# hackeeg-shield.net
KiCad netlist of a schematic drawn in EAGLE
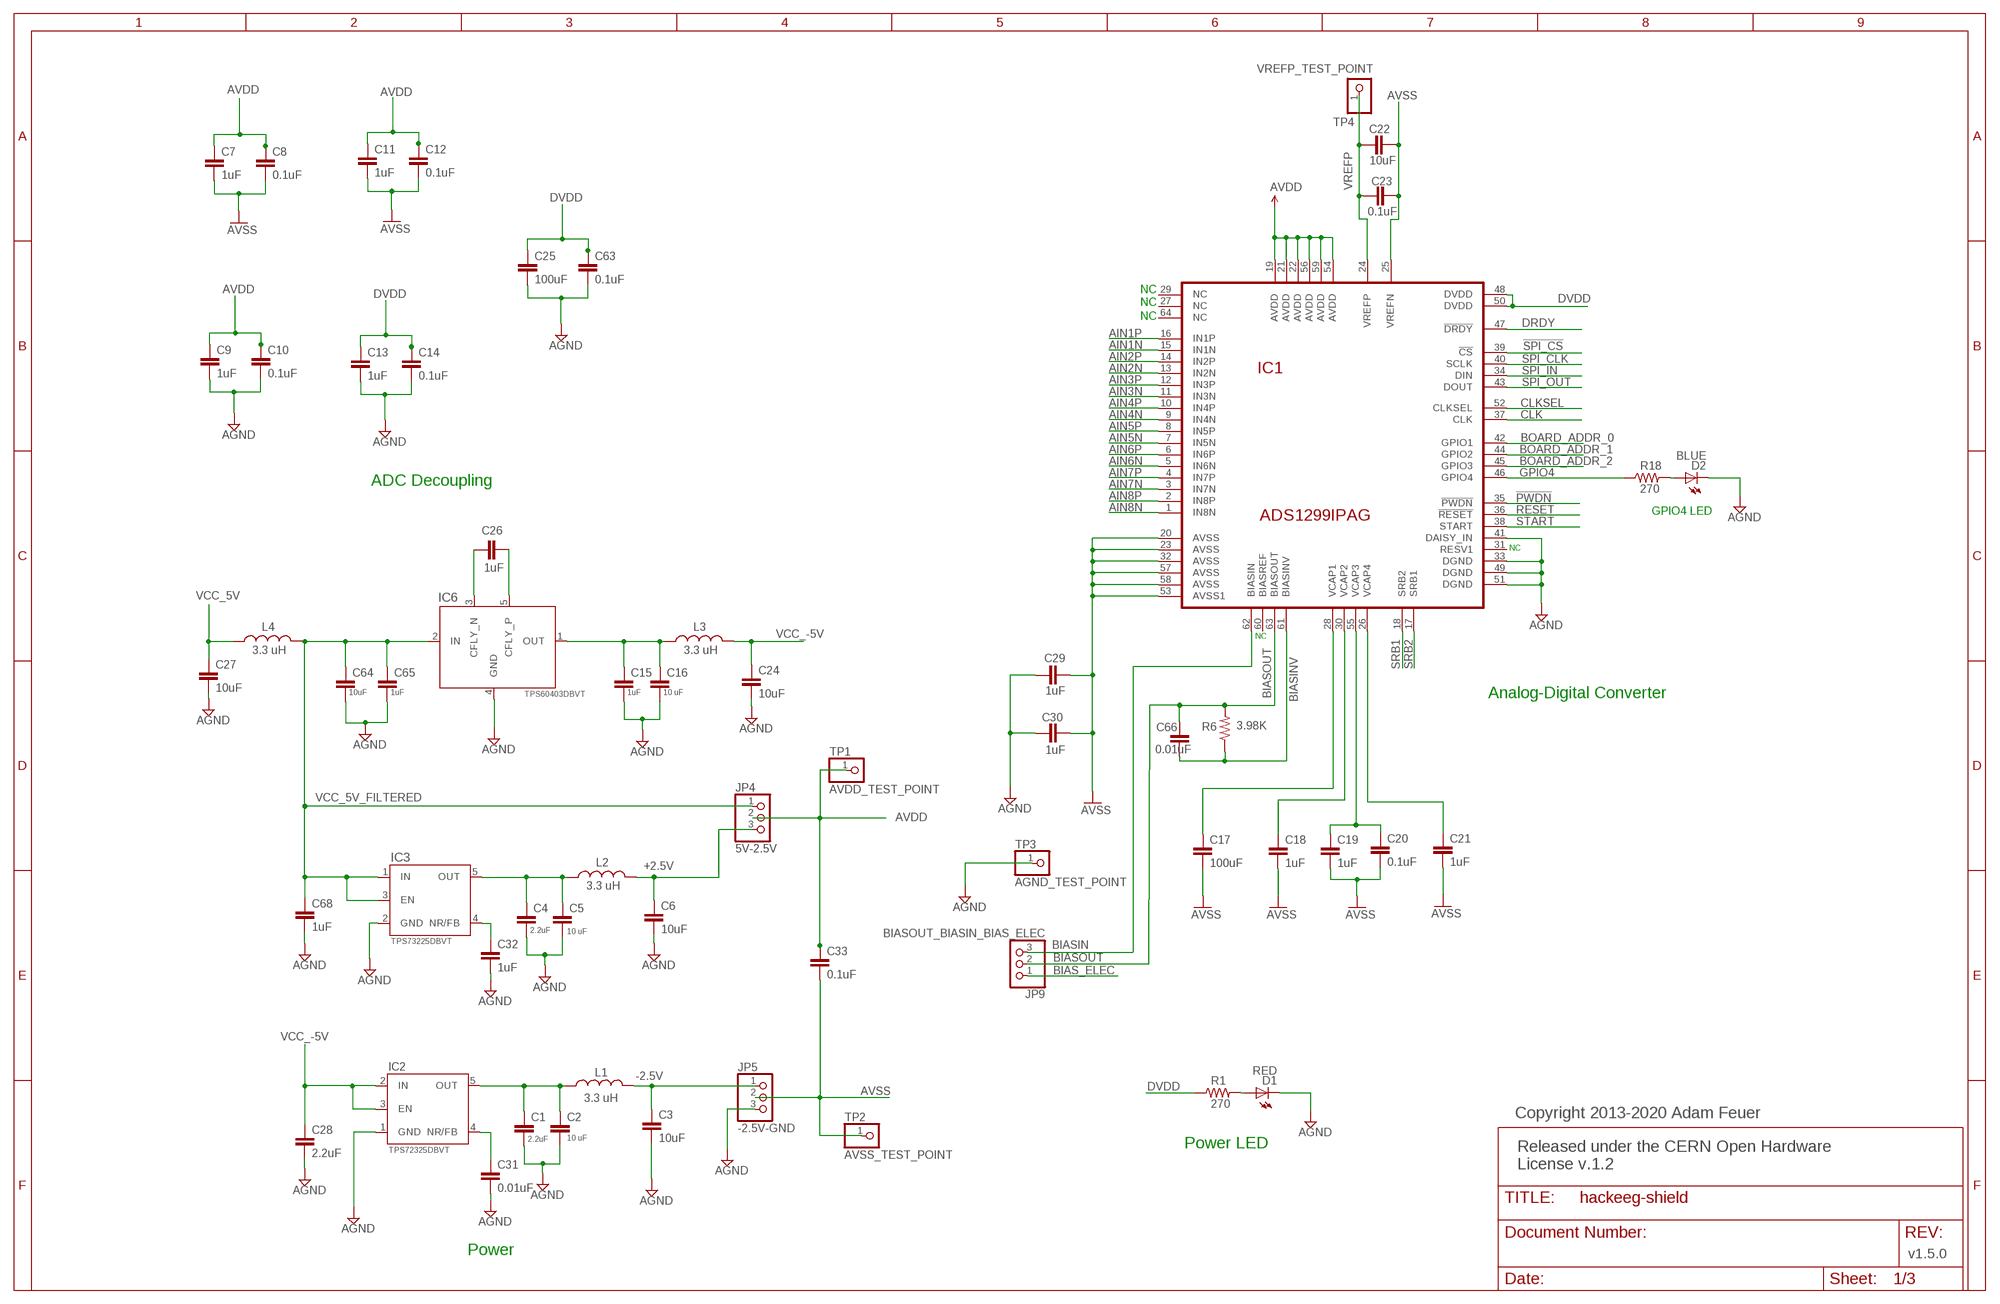
[diagram p0: schematic, sheet 1]
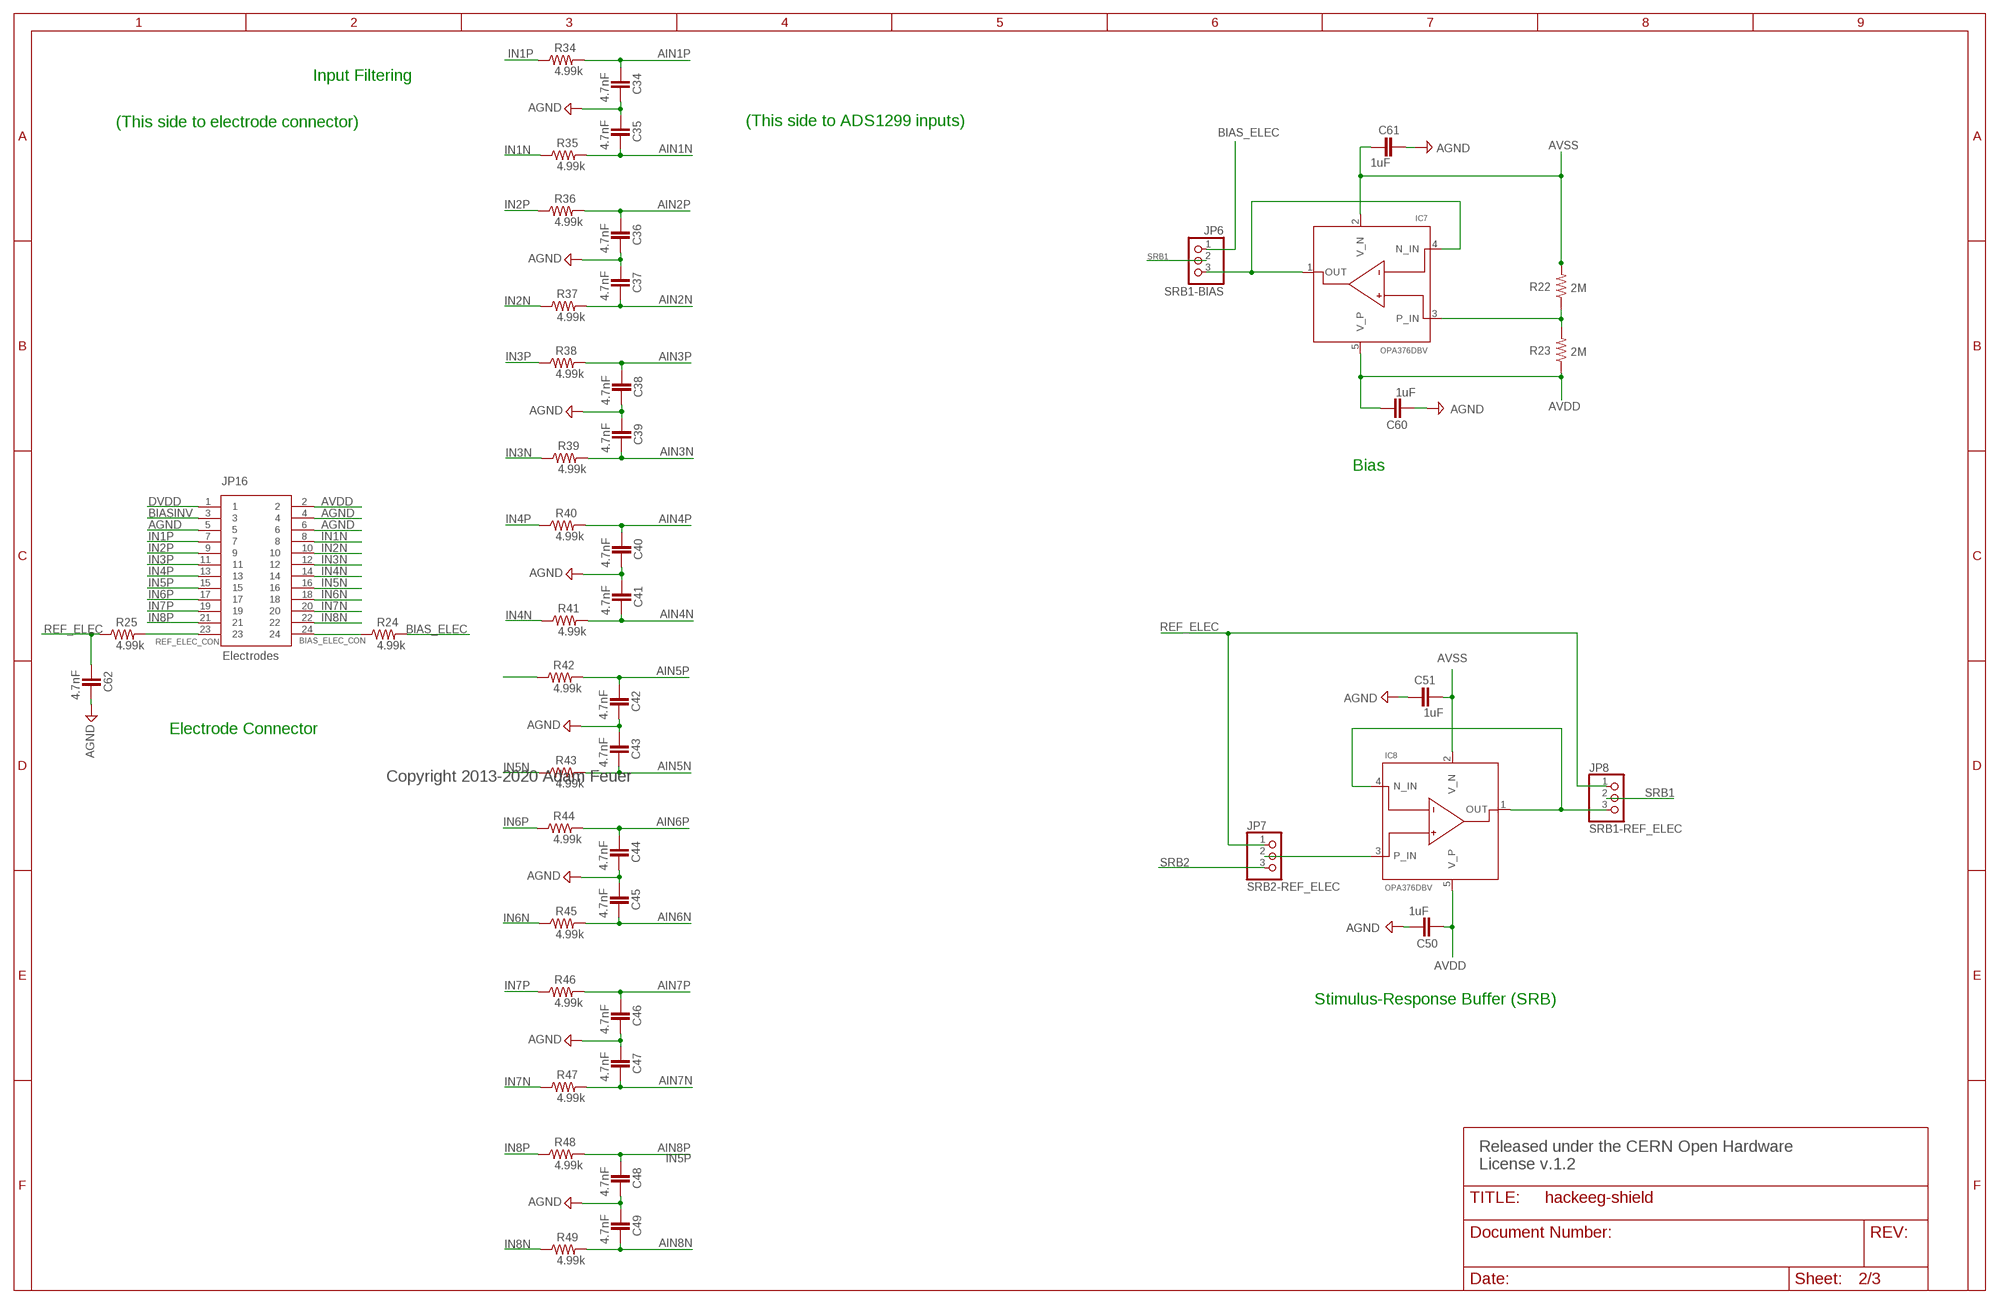
[diagram p1: schematic, sheet 2]
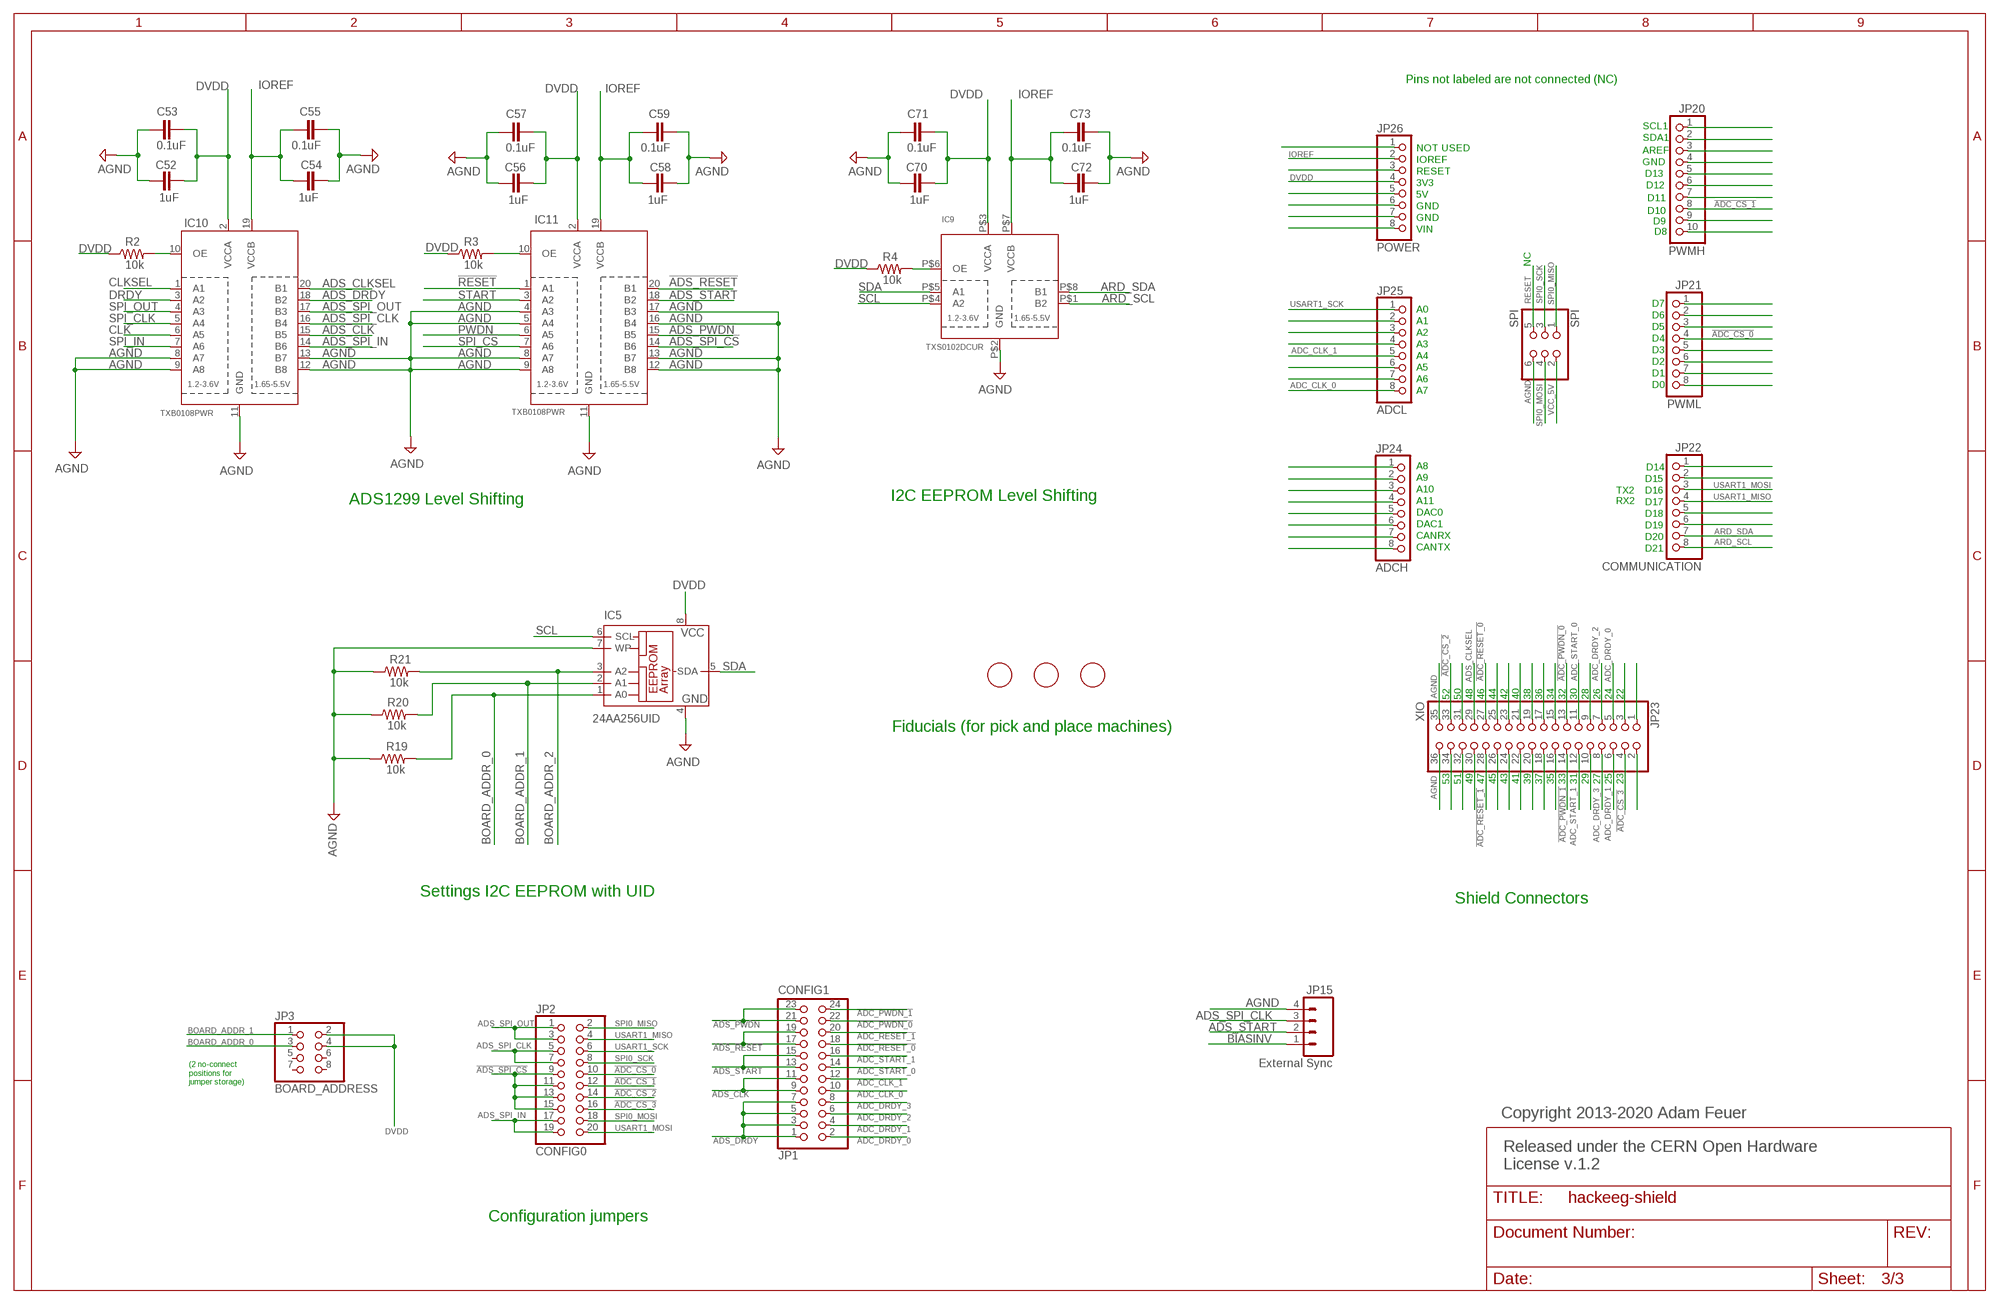
[diagram p2: schematic, sheet 3]

(export (version "E")
  (design (tool "Eeschema 10.0.6"))
  (components
    (comp (ref "C52")
      (value "1uF")
      (footprint "eagle-import:0603-CAP")
      (libsource (lib "eagle-import") (part "CAP0603-CAP"))
    )
    (comp (ref "C53")
      (value "0.1uF")
      (footprint "eagle-import:0603-CAP")
      (libsource (lib "eagle-import") (part "CAP0603-CAP"))
    )
    (comp (ref "C54")
      (value "1uF")
      (footprint "eagle-import:0603-CAP")
      (libsource (lib "eagle-import") (part "CAP0603-CAP"))
    )
    (comp (ref "C55")
      (value "0.1uF")
      (footprint "eagle-import:0603-CAP")
      (libsource (lib "eagle-import") (part "CAP0603-CAP"))
    )
    (comp (ref "C56")
      (value "1uF")
      (footprint "eagle-import:0603-CAP")
      (libsource (lib "eagle-import") (part "CAP0603-CAP"))
    )
    (comp (ref "C57")
      (value "0.1uF")
      (footprint "eagle-import:0603-CAP")
      (libsource (lib "eagle-import") (part "CAP0603-CAP"))
    )
    (comp (ref "C58")
      (value "1uF")
      (footprint "eagle-import:0603-CAP")
      (libsource (lib "eagle-import") (part "CAP0603-CAP"))
    )
    (comp (ref "C59")
      (value "0.1uF")
      (footprint "eagle-import:0603-CAP")
      (libsource (lib "eagle-import") (part "CAP0603-CAP"))
    )
    (comp (ref "C70")
      (value "1uF")
      (footprint "eagle-import:0603-CAP")
      (libsource (lib "eagle-import") (part "CAP0603-CAP"))
    )
    (comp (ref "C71")
      (value "0.1uF")
      (footprint "eagle-import:0603-CAP")
      (libsource (lib "eagle-import") (part "CAP0603-CAP"))
    )
    (comp (ref "C72")
      (value "1uF")
      (footprint "eagle-import:0603-CAP")
      (libsource (lib "eagle-import") (part "CAP0603-CAP"))
    )
    (comp (ref "C73")
      (value "0.1uF")
      (footprint "eagle-import:0603-CAP")
      (libsource (lib "eagle-import") (part "CAP0603-CAP"))
    )
    (comp (ref "IC5")
      (value "24AA256UID")
      (footprint "eagle-import:SO-08")
      (fields (field (name "MF") "MICROCHIP") (field (name "MPN") "24LC256-I/SN"))
      (libsource (lib "eagle-import") (part "24SNLC256"))
    )
    (comp (ref "IC9")
      (value "TXS0102DCUR")
      (footprint "eagle-import:VFSOP-8")
      (libsource (lib "eagle-import") (part "TXS0102"))
    )
    (comp (ref "IC10")
      (value "TXB0108PWR")
      (footprint "eagle-import:TSSOP20")
      (libsource (lib "eagle-import") (part "TXB0108PWR"))
    )
    (comp (ref "IC11")
      (value "TXB0108PWR")
      (footprint "eagle-import:TSSOP20")
      (libsource (lib "eagle-import") (part "TXB0108PWR"))
    )
    (comp (ref "JP1")
      (value "CONFIG1")
      (footprint "eagle-import:2X12")
      (libsource (lib "eagle-import") (part "PINHD-2X12"))
    )
    (comp (ref "JP2")
      (value "CONFIG0")
      (footprint "eagle-import:2X10")
      (libsource (lib "eagle-import") (part "PINHD-2X10"))
    )
    (comp (ref "JP3")
      (value "BOARD_ADDRESS")
      (footprint "eagle-import:2X04")
      (libsource (lib "eagle-import") (part "PINHD-2X4"))
    )
    (comp (ref "JP15")
      (value "External Sync")
      (footprint "eagle-import:JST-4-PTH")
      (libsource (lib "eagle-import") (part "M04JST-PTH"))
    )
    (comp (ref "JP20")
      (value "PWMH")
      (footprint "eagle-import:1X10")
      (libsource (lib "eagle-import") (part "PINHD-1X10"))
    )
    (comp (ref "JP21")
      (value "PWML")
      (footprint "eagle-import:1X08")
      (libsource (lib "eagle-import") (part "PINHD-1X8"))
    )
    (comp (ref "JP22")
      (value "COMMUNICATION")
      (footprint "eagle-import:1X08")
      (libsource (lib "eagle-import") (part "PINHD-1X8"))
    )
    (comp (ref "JP23")
      (value "XIO")
      (footprint "eagle-import:2X18")
      (libsource (lib "eagle-import") (part "PINHD-2X18"))
    )
    (comp (ref "JP24")
      (value "ADCH")
      (footprint "eagle-import:1X08")
      (libsource (lib "eagle-import") (part "PINHD-1X8"))
    )
    (comp (ref "JP25")
      (value "ADCL")
      (footprint "eagle-import:1X08")
      (libsource (lib "eagle-import") (part "PINHD-1X8"))
    )
    (comp (ref "JP26")
      (value "POWER")
      (footprint "eagle-import:1X08")
      (libsource (lib "eagle-import") (part "PINHD-1X8"))
    )
    (comp (ref "R2")
      (value "10k")
      (footprint "eagle-import:0603-RES")
      (libsource (lib "eagle-import") (part "RESISTOR0603-RES"))
    )
    (comp (ref "R3")
      (value "10k")
      (footprint "eagle-import:0603-RES")
      (libsource (lib "eagle-import") (part "RESISTOR0603-RES"))
    )
    (comp (ref "R4")
      (value "10k")
      (footprint "eagle-import:0603-RES")
      (libsource (lib "eagle-import") (part "RESISTOR0603-RES"))
    )
    (comp (ref "R19")
      (value "10k")
      (footprint "eagle-import:0603-RES")
      (libsource (lib "eagle-import") (part "RESISTOR0603-RES"))
    )
    (comp (ref "R20")
      (value "10k")
      (footprint "eagle-import:0603-RES")
      (libsource (lib "eagle-import") (part "RESISTOR0603-RES"))
    )
    (comp (ref "R21")
      (value "10k")
      (footprint "eagle-import:0603-RES")
      (libsource (lib "eagle-import") (part "RESISTOR0603-RES"))
    )
    (comp (ref "SPI")
      (value "SPI")
      (footprint "eagle-import:2X03")
      (libsource (lib "eagle-import") (part "PINHD-2X3"))
    )
    (comp (ref "U$2")
      (value "FIDUCIAL")
      (footprint "eagle-import:FIDUCIAL_1MM")
      (libsource (lib "eagle-import") (part "FIDUCIAL"))
    )
    (comp (ref "U$5")
      (value "FIDUCIAL")
      (footprint "eagle-import:FIDUCIAL_1MM")
      (libsource (lib "eagle-import") (part "FIDUCIAL"))
    )
    (comp (ref "U$6")
      (value "FIDUCIAL")
      (footprint "eagle-import:FIDUCIAL_1MM")
      (libsource (lib "eagle-import") (part "FIDUCIAL"))
    )
    (comp (ref "C1")
      (value "2.2uF")
      (footprint "eagle-import:0603-CAP")
      (libsource (lib "eagle-import") (part "CAP0603-CAP"))
    )
    (comp (ref "C2")
      (value "10 uF")
      (footprint "eagle-import:0603-CAP")
      (libsource (lib "eagle-import") (part "CAP0603-CAP"))
    )
    (comp (ref "C3")
      (value "10uF")
      (footprint "eagle-import:0603-CAP")
      (libsource (lib "eagle-import") (part "CAP0603-CAP"))
    )
    (comp (ref "C4")
      (value "2.2uF")
      (footprint "eagle-import:0603-CAP")
      (libsource (lib "eagle-import") (part "CAP0603-CAP"))
    )
    (comp (ref "C5")
      (value "10 uF")
      (footprint "eagle-import:0603-CAP")
      (libsource (lib "eagle-import") (part "CAP0603-CAP"))
    )
    (comp (ref "C6")
      (value "10uF")
      (footprint "eagle-import:0603-CAP")
      (libsource (lib "eagle-import") (part "CAP0603-CAP"))
    )
    (comp (ref "C7")
      (value "1uF")
      (footprint "eagle-import:0603-CAP")
      (libsource (lib "eagle-import") (part "CAP0603-CAP"))
    )
    (comp (ref "C8")
      (value "0.1uF")
      (footprint "eagle-import:0603-CAP")
      (libsource (lib "eagle-import") (part "CAP0603-CAP"))
    )
    (comp (ref "C9")
      (value "1uF")
      (footprint "eagle-import:0603-CAP")
      (libsource (lib "eagle-import") (part "CAP0603-CAP"))
    )
    (comp (ref "C10")
      (value "0.1uF")
      (footprint "eagle-import:0603-CAP")
      (libsource (lib "eagle-import") (part "CAP0603-CAP"))
    )
    (comp (ref "C11")
      (value "1uF")
      (footprint "eagle-import:0603-CAP")
      (libsource (lib "eagle-import") (part "CAP0603-CAP"))
    )
    (comp (ref "C12")
      (value "0.1uF")
      (footprint "eagle-import:0603-CAP")
      (libsource (lib "eagle-import") (part "CAP0603-CAP"))
    )
    (comp (ref "C13")
      (value "1uF")
      (footprint "eagle-import:0603-CAP")
      (libsource (lib "eagle-import") (part "CAP0603-CAP"))
    )
    (comp (ref "C14")
      (value "0.1uF")
      (footprint "eagle-import:0603-CAP")
      (libsource (lib "eagle-import") (part "CAP0603-CAP"))
    )
    (comp (ref "C15")
      (value "1uF")
      (footprint "eagle-import:0603-CAP")
      (libsource (lib "eagle-import") (part "CAP0603-CAP"))
    )
    (comp (ref "C16")
      (value "10 uF")
      (footprint "eagle-import:0603-CAP")
      (libsource (lib "eagle-import") (part "CAP0603-CAP"))
    )
    (comp (ref "C17")
      (value "100uF")
      (footprint "eagle-import:1210")
      (libsource (lib "eagle-import") (part "CAP1210"))
    )
    (comp (ref "C18")
      (value "1uF")
      (footprint "eagle-import:0603-CAP")
      (libsource (lib "eagle-import") (part "CAP0603-CAP"))
    )
    (comp (ref "C19")
      (value "1uF")
      (footprint "eagle-import:0603-CAP")
      (libsource (lib "eagle-import") (part "CAP0603-CAP"))
    )
    (comp (ref "C20")
      (value "0.1uF")
      (footprint "eagle-import:0603-CAP")
      (libsource (lib "eagle-import") (part "CAP0603-CAP"))
    )
    (comp (ref "C21")
      (value "1uF")
      (footprint "eagle-import:0603-CAP")
      (libsource (lib "eagle-import") (part "CAP0603-CAP"))
    )
    (comp (ref "C22")
      (value "10uF")
      (footprint "eagle-import:0603-CAP")
      (libsource (lib "eagle-import") (part "CAP0603-CAP"))
    )
    (comp (ref "C23")
      (value "0.1uF")
      (footprint "eagle-import:0603-CAP")
      (libsource (lib "eagle-import") (part "CAP0603-CAP"))
    )
    (comp (ref "C24")
      (value "10uF")
      (footprint "eagle-import:0603-CAP")
      (libsource (lib "eagle-import") (part "CAP0603-CAP"))
    )
    (comp (ref "C25")
      (value "100uF")
      (footprint "eagle-import:1210")
      (libsource (lib "eagle-import") (part "CAP1210"))
    )
    (comp (ref "C26")
      (value "1uF")
      (footprint "eagle-import:0603-CAP")
      (libsource (lib "eagle-import") (part "CAP0603-CAP"))
    )
    (comp (ref "C27")
      (value "10uF")
      (footprint "eagle-import:0603-CAP")
      (libsource (lib "eagle-import") (part "CAP0603-CAP"))
    )
    (comp (ref "C28")
      (value "2.2uF")
      (footprint "eagle-import:0603-CAP")
      (libsource (lib "eagle-import") (part "CAP0603-CAP"))
    )
    (comp (ref "C29")
      (value "1uF")
      (footprint "eagle-import:0603-CAP")
      (libsource (lib "eagle-import") (part "CAP0603-CAP"))
    )
    (comp (ref "C30")
      (value "1uF")
      (footprint "eagle-import:0603-CAP")
      (libsource (lib "eagle-import") (part "CAP0603-CAP"))
    )
    (comp (ref "C31")
      (value "0.01uF")
      (footprint "eagle-import:0603-CAP")
      (libsource (lib "eagle-import") (part "CAP0603-CAP"))
    )
    (comp (ref "C32")
      (value "1uF")
      (footprint "eagle-import:0603-CAP")
      (libsource (lib "eagle-import") (part "CAP0603-CAP"))
    )
    (comp (ref "C33")
      (value "0.1uF")
      (footprint "eagle-import:0603-CAP")
      (libsource (lib "eagle-import") (part "CAP0603-CAP"))
    )
    (comp (ref "C63")
      (value "0.1uF")
      (footprint "eagle-import:0603-CAP")
      (libsource (lib "eagle-import") (part "CAP0603-CAP"))
    )
    (comp (ref "C64")
      (value "10uF")
      (footprint "eagle-import:0603-CAP")
      (libsource (lib "eagle-import") (part "CAP0603-CAP"))
    )
    (comp (ref "C65")
      (value "1uF")
      (footprint "eagle-import:0603-CAP")
      (libsource (lib "eagle-import") (part "CAP0603-CAP"))
    )
    (comp (ref "C66")
      (value "0.01uF")
      (footprint "eagle-import:0603-CAP")
      (libsource (lib "eagle-import") (part "CAP0603-CAP"))
    )
    (comp (ref "C68")
      (value "1uF")
      (footprint "eagle-import:0603-CAP")
      (libsource (lib "eagle-import") (part "CAP0603-CAP"))
    )
    (comp (ref "D1")
      (value "RED")
      (footprint "eagle-import:LED-1206")
      (libsource (lib "eagle-import") (part "LED-RED1206"))
    )
    (comp (ref "D2")
      (value "BLUE")
      (footprint "eagle-import:LED-1206")
      (libsource (lib "eagle-import") (part "LED-WHITE"))
    )
    (comp (ref "IC1")
      (value "ADS1299IPAG")
      (footprint "eagle-import:TQFP64")
      (libsource (lib "eagle-import") (part "ADS1299PAG"))
    )
    (comp (ref "IC2")
      (value "TPS72325DBVT")
      (footprint "eagle-import:SOT23-5")
      (libsource (lib "eagle-import") (part "TPS723xx_TPS732XXDBV"))
    )
    (comp (ref "IC3")
      (value "TPS73225DBVT")
      (footprint "eagle-import:SOT23-5")
      (libsource (lib "eagle-import") (part "TPS732XXDBV"))
    )
    (comp (ref "IC6")
      (value "TPS60403DBVT")
      (footprint "eagle-import:SOT23-5")
      (libsource (lib "eagle-import") (part "TPS604XXDBV"))
    )
    (comp (ref "JP4")
      (value "5V-2.5V")
      (footprint "eagle-import:1X03")
      (libsource (lib "eagle-import") (part "headers_PINHD-1X3"))
    )
    (comp (ref "JP5")
      (value "-2.5V-GND")
      (footprint "eagle-import:1X03")
      (libsource (lib "eagle-import") (part "headers_PINHD-1X3"))
    )
    (comp (ref "JP9")
      (value "BIASOUT_BIASIN_BIAS_ELEC")
      (footprint "eagle-import:1X03")
      (libsource (lib "eagle-import") (part "headers_PINHD-1X3"))
    )
    (comp (ref "L1")
      (value "3.3 uH")
      (footprint "eagle-import:0805")
      (libsource (lib "eagle-import") (part "INDUCTOR0805"))
    )
    (comp (ref "L2")
      (value "3.3 uH")
      (footprint "eagle-import:0805")
      (libsource (lib "eagle-import") (part "INDUCTOR0805"))
    )
    (comp (ref "L3")
      (value "3.3 uH")
      (footprint "eagle-import:0805")
      (libsource (lib "eagle-import") (part "INDUCTOR0805"))
    )
    (comp (ref "L4")
      (value "3.3 uH")
      (footprint "eagle-import:0805")
      (libsource (lib "eagle-import") (part "INDUCTOR0805"))
    )
    (comp (ref "R1")
      (value "270")
      (footprint "eagle-import:0603-RES")
      (libsource (lib "eagle-import") (part "RESISTOR0603-RES"))
    )
    (comp (ref "R6")
      (value "3.98K")
      (footprint "eagle-import:0603-RES")
      (libsource (lib "eagle-import") (part "RESISTOR0603-RES"))
    )
    (comp (ref "R18")
      (value "270")
      (footprint "eagle-import:0603-RES")
      (libsource (lib "eagle-import") (part "RESISTOR0603-RES"))
    )
    (comp (ref "TP1")
      (value "AVDD_TEST_POINT")
      (footprint "eagle-import:1X01")
      (libsource (lib "eagle-import") (part "PINHD-1X1"))
    )
    (comp (ref "TP2")
      (value "AVSS_TEST_POINT")
      (footprint "eagle-import:1X01")
      (libsource (lib "eagle-import") (part "PINHD-1X1"))
    )
    (comp (ref "TP3")
      (value "AGND_TEST_POINT")
      (footprint "eagle-import:1X01")
      (libsource (lib "eagle-import") (part "PINHD-1X1"))
    )
    (comp (ref "TP4")
      (value "VREFP_TEST_POINT")
      (footprint "eagle-import:1X01")
      (libsource (lib "eagle-import") (part "PINHD-1X1"))
    )
    (comp (ref "C34")
      (value "4.7nF")
      (footprint "eagle-import:0603-CAP")
      (libsource (lib "eagle-import") (part "CAP0603-CAP"))
    )
    (comp (ref "C35")
      (value "4.7nF")
      (footprint "eagle-import:0603-CAP")
      (libsource (lib "eagle-import") (part "CAP0603-CAP"))
    )
    (comp (ref "C36")
      (value "4.7nF")
      (footprint "eagle-import:0603-CAP")
      (libsource (lib "eagle-import") (part "CAP0603-CAP"))
    )
    (comp (ref "C37")
      (value "4.7nF")
      (footprint "eagle-import:0603-CAP")
      (libsource (lib "eagle-import") (part "CAP0603-CAP"))
    )
    (comp (ref "C38")
      (value "4.7nF")
      (footprint "eagle-import:0603-CAP")
      (libsource (lib "eagle-import") (part "CAP0603-CAP"))
    )
    (comp (ref "C39")
      (value "4.7nF")
      (footprint "eagle-import:0603-CAP")
      (libsource (lib "eagle-import") (part "CAP0603-CAP"))
    )
    (comp (ref "C40")
      (value "4.7nF")
      (footprint "eagle-import:0603-CAP")
      (libsource (lib "eagle-import") (part "CAP0603-CAP"))
    )
    (comp (ref "C41")
      (value "4.7nF")
      (footprint "eagle-import:0603-CAP")
      (libsource (lib "eagle-import") (part "CAP0603-CAP"))
    )
    (comp (ref "C42")
      (value "4.7nF")
      (footprint "eagle-import:0603-CAP")
      (libsource (lib "eagle-import") (part "CAP0603-CAP"))
    )
    (comp (ref "C43")
      (value "4.7nF")
      (footprint "eagle-import:0603-CAP")
      (libsource (lib "eagle-import") (part "CAP0603-CAP"))
    )
    (comp (ref "C44")
      (value "4.7nF")
      (footprint "eagle-import:0603-CAP")
      (libsource (lib "eagle-import") (part "CAP0603-CAP"))
    )
    (comp (ref "C45")
      (value "4.7nF")
      (footprint "eagle-import:0603-CAP")
      (libsource (lib "eagle-import") (part "CAP0603-CAP"))
    )
    (comp (ref "C46")
      (value "4.7nF")
      (footprint "eagle-import:0603-CAP")
      (libsource (lib "eagle-import") (part "CAP0603-CAP"))
    )
    (comp (ref "C47")
      (value "4.7nF")
      (footprint "eagle-import:0603-CAP")
      (libsource (lib "eagle-import") (part "CAP0603-CAP"))
    )
    (comp (ref "C48")
      (value "4.7nF")
      (footprint "eagle-import:0603-CAP")
      (libsource (lib "eagle-import") (part "CAP0603-CAP"))
    )
    (comp (ref "C49")
      (value "4.7nF")
      (footprint "eagle-import:0603-CAP")
      (libsource (lib "eagle-import") (part "CAP0603-CAP"))
    )
    (comp (ref "C50")
      (value "1uF")
      (footprint "eagle-import:0603-CAP")
      (libsource (lib "eagle-import") (part "CAP0603-CAP"))
    )
    (comp (ref "C51")
      (value "1uF")
      (footprint "eagle-import:0603-CAP")
      (libsource (lib "eagle-import") (part "CAP0603-CAP"))
    )
    (comp (ref "C60")
      (value "1uF")
      (footprint "eagle-import:0603-CAP")
      (libsource (lib "eagle-import") (part "CAP0603-CAP"))
    )
    (comp (ref "C61")
      (value "1uF")
      (footprint "eagle-import:0603-CAP")
      (libsource (lib "eagle-import") (part "CAP0603-CAP"))
    )
    (comp (ref "C62")
      (value "4.7nF")
      (footprint "eagle-import:0603-CAP")
      (libsource (lib "eagle-import") (part "CAP0603-CAP"))
    )
    (comp (ref "IC7")
      (value "OPA376DBV")
      (footprint "eagle-import:SOT23-5")
      (libsource (lib "eagle-import") (part "OPA376DBV"))
    )
    (comp (ref "IC8")
      (value "OPA376DBV")
      (footprint "eagle-import:SOT23-5")
      (libsource (lib "eagle-import") (part "OPA376DBV"))
    )
    (comp (ref "JP6")
      (value "SRB1-BIAS")
      (footprint "eagle-import:1X03")
      (libsource (lib "eagle-import") (part "PINHD-1X3"))
    )
    (comp (ref "JP7")
      (value "SRB2-REF_ELEC")
      (footprint "eagle-import:1X03")
      (libsource (lib "eagle-import") (part "PINHD-1X3"))
    )
    (comp (ref "JP8")
      (value "SRB1-REF_ELEC")
      (footprint "eagle-import:1X03")
      (libsource (lib "eagle-import") (part "PINHD-1X3"))
    )
    (comp (ref "JP16")
      (value "Electrodes")
      (footprint "eagle-import:OST_302-R241")
      (fields (field (name "MF") "On Shore") (field (name "MP") "302-R241"))
      (libsource (lib "eagle-import") (part "302-R241"))
    )
    (comp (ref "R22")
      (value "2M")
      (footprint "eagle-import:0603-RES")
      (libsource (lib "eagle-import") (part "RESISTOR0603-RES"))
    )
    (comp (ref "R23")
      (value "2M")
      (footprint "eagle-import:0603-RES")
      (libsource (lib "eagle-import") (part "RESISTOR0603-RES"))
    )
    (comp (ref "R24")
      (value "4.99k")
      (footprint "eagle-import:0603-RES")
      (libsource (lib "eagle-import") (part "RESISTOR0603-RES"))
    )
    (comp (ref "R25")
      (value "4.99k")
      (footprint "eagle-import:0603-RES")
      (libsource (lib "eagle-import") (part "RESISTOR0603-RES"))
    )
    (comp (ref "R34")
      (value "4.99k")
      (footprint "eagle-import:0603-RES")
      (libsource (lib "eagle-import") (part "RESISTOR0603-RES"))
    )
    (comp (ref "R35")
      (value "4.99k")
      (footprint "eagle-import:0603-RES")
      (libsource (lib "eagle-import") (part "RESISTOR0603-RES"))
    )
    (comp (ref "R36")
      (value "4.99k")
      (footprint "eagle-import:0603-RES")
      (libsource (lib "eagle-import") (part "RESISTOR0603-RES"))
    )
    (comp (ref "R37")
      (value "4.99k")
      (footprint "eagle-import:0603-RES")
      (libsource (lib "eagle-import") (part "RESISTOR0603-RES"))
    )
    (comp (ref "R38")
      (value "4.99k")
      (footprint "eagle-import:0603-RES")
      (libsource (lib "eagle-import") (part "RESISTOR0603-RES"))
    )
    (comp (ref "R39")
      (value "4.99k")
      (footprint "eagle-import:0603-RES")
      (libsource (lib "eagle-import") (part "RESISTOR0603-RES"))
    )
    (comp (ref "R40")
      (value "4.99k")
      (footprint "eagle-import:0603-RES")
      (libsource (lib "eagle-import") (part "RESISTOR0603-RES"))
    )
    (comp (ref "R41")
      (value "4.99k")
      (footprint "eagle-import:0603-RES")
      (libsource (lib "eagle-import") (part "RESISTOR0603-RES"))
    )
    (comp (ref "R42")
      (value "4.99k")
      (footprint "eagle-import:0603-RES")
      (libsource (lib "eagle-import") (part "RESISTOR0603-RES"))
    )
    (comp (ref "R43")
      (value "4.99k")
      (footprint "eagle-import:0603-RES")
      (libsource (lib "eagle-import") (part "RESISTOR0603-RES"))
    )
    (comp (ref "R44")
      (value "4.99k")
      (footprint "eagle-import:0603-RES")
      (libsource (lib "eagle-import") (part "RESISTOR0603-RES"))
    )
    (comp (ref "R45")
      (value "4.99k")
      (footprint "eagle-import:0603-RES")
      (libsource (lib "eagle-import") (part "RESISTOR0603-RES"))
    )
    (comp (ref "R46")
      (value "4.99k")
      (footprint "eagle-import:0603-RES")
      (libsource (lib "eagle-import") (part "RESISTOR0603-RES"))
    )
    (comp (ref "R47")
      (value "4.99k")
      (footprint "eagle-import:0603-RES")
      (libsource (lib "eagle-import") (part "RESISTOR0603-RES"))
    )
    (comp (ref "R48")
      (value "4.99k")
      (footprint "eagle-import:0603-RES")
      (libsource (lib "eagle-import") (part "RESISTOR0603-RES"))
    )
    (comp (ref "R49")
      (value "4.99k")
      (footprint "eagle-import:0603-RES")
      (libsource (lib "eagle-import") (part "RESISTOR0603-RES"))
    )
  )
  (nets
    (net (code "1") (name "+2.5V") (class "Default")
      (node (ref "C6") (pin "1") (pinfunction "1_1") (pintype "passive"))
      (node (ref "JP4") (pin "3") (pinfunction "3_3") (pintype "passive"))
      (node (ref "L2") (pin "2") (pinfunction "2_2") (pintype "passive"))
    )
    (net (code "2") (name "-2.5V") (class "Default")
      (node (ref "C3") (pin "1") (pinfunction "1_1") (pintype "passive"))
      (node (ref "JP5") (pin "1") (pinfunction "1_1") (pintype "passive"))
      (node (ref "L1") (pin "2") (pinfunction "2_2") (pintype "passive"))
    )
    (net (code "3") (name "ADC_CLK_0") (class "Default")
      (node (ref "JP1") (pin "10") (pinfunction "10_10") (pintype "passive"))
      (node (ref "JP25") (pin "8") (pinfunction "8_8") (pintype "passive"))
    )
    (net (code "4") (name "ADC_CLK_1") (class "Default")
      (node (ref "JP1") (pin "12") (pinfunction "12_12") (pintype "passive"))
      (node (ref "JP25") (pin "5") (pinfunction "5_5") (pintype "passive"))
    )
    (net (code "5") (name "ADC_DRDY_0") (class "Default")
      (node (ref "JP1") (pin "2") (pinfunction "2_2") (pintype "passive"))
      (node (ref "JP23") (pin "5") (pinfunction "5_5") (pintype "passive"))
    )
    (net (code "6") (name "ADC_DRDY_1") (class "Default")
      (node (ref "JP1") (pin "4") (pinfunction "4_4") (pintype "passive"))
      (node (ref "JP23") (pin "6") (pinfunction "6_6") (pintype "passive"))
    )
    (net (code "7") (name "ADC_DRDY_2") (class "Default")
      (node (ref "JP1") (pin "6") (pinfunction "6_6") (pintype "passive"))
      (node (ref "JP23") (pin "7") (pinfunction "7_7") (pintype "passive"))
    )
    (net (code "8") (name "ADC_DRDY_3") (class "Default")
      (node (ref "JP1") (pin "8") (pinfunction "8_8") (pintype "passive"))
      (node (ref "JP23") (pin "8") (pinfunction "8_8") (pintype "passive"))
    )
    (net (code "9") (name "ADC_START_0") (class "Default")
      (node (ref "JP1") (pin "14") (pinfunction "14_14") (pintype "passive"))
      (node (ref "JP23") (pin "11") (pinfunction "11_11") (pintype "passive"))
    )
    (net (code "10") (name "ADC_START_1") (class "Default")
      (node (ref "JP1") (pin "16") (pinfunction "16_16") (pintype "passive"))
      (node (ref "JP23") (pin "12") (pinfunction "12_12") (pintype "passive"))
    )
    (net (code "11") (name "ADS_CLK") (class "Default")
      (node (ref "IC10") (pin "15") (pinfunction "B5_15") (pintype "bidirectional"))
      (node (ref "JP1") (pin "11") (pinfunction "11_11") (pintype "passive"))
      (node (ref "JP1") (pin "9") (pinfunction "9_9") (pintype "passive"))
    )
    (net (code "12") (name "ADS_CLKSEL") (class "Default")
      (node (ref "IC10") (pin "20") (pinfunction "B1_20") (pintype "bidirectional"))
      (node (ref "JP23") (pin "29") (pinfunction "29_29") (pintype "passive"))
    )
    (net (code "13") (name "ADS_DRDY") (class "Default")
      (node (ref "IC10") (pin "18") (pinfunction "B2_18") (pintype "bidirectional"))
      (node (ref "JP1") (pin "1") (pinfunction "1_1") (pintype "passive"))
      (node (ref "JP1") (pin "3") (pinfunction "3_3") (pintype "passive"))
      (node (ref "JP1") (pin "5") (pinfunction "5_5") (pintype "passive"))
      (node (ref "JP1") (pin "7") (pinfunction "7_7") (pintype "passive"))
    )
    (net (code "14") (name "ADS_SPI_CLK") (class "Default")
      (node (ref "IC10") (pin "16") (pinfunction "B4_16") (pintype "bidirectional"))
      (node (ref "JP15") (pin "3") (pinfunction "3_3") (pintype "passive"))
      (node (ref "JP2") (pin "5") (pinfunction "5_5") (pintype "passive"))
      (node (ref "JP2") (pin "7") (pinfunction "7_7") (pintype "passive"))
    )
    (net (code "15") (name "ADS_SPI_IN") (class "Default")
      (node (ref "IC10") (pin "14") (pinfunction "B6_14") (pintype "bidirectional"))
      (node (ref "JP2") (pin "17") (pinfunction "17_17") (pintype "passive"))
      (node (ref "JP2") (pin "19") (pinfunction "19_19") (pintype "passive"))
    )
    (net (code "16") (name "ADS_SPI_OUT") (class "Default")
      (node (ref "IC10") (pin "17") (pinfunction "B3_17") (pintype "bidirectional"))
      (node (ref "JP2") (pin "1") (pinfunction "1_1") (pintype "passive"))
      (node (ref "JP2") (pin "3") (pinfunction "3_3") (pintype "passive"))
    )
    (net (code "17") (name "ADS_START") (class "Default")
      (node (ref "IC11") (pin "18") (pinfunction "B2_18") (pintype "bidirectional"))
      (node (ref "JP1") (pin "13") (pinfunction "13_13") (pintype "passive"))
      (node (ref "JP1") (pin "15") (pinfunction "15_15") (pintype "passive"))
      (node (ref "JP15") (pin "2") (pinfunction "2_2") (pintype "passive"))
    )
    (net (code "18") (name "AGND") (class "Default")
      (node (ref "C1") (pin "2") (pinfunction "2_2") (pintype "passive"))
      (node (ref "C10") (pin "2") (pinfunction "2_2") (pintype "passive"))
      (node (ref "C13") (pin "2") (pinfunction "2_2") (pintype "passive"))
      (node (ref "C14") (pin "2") (pinfunction "2_2") (pintype "passive"))
      (node (ref "C15") (pin "2") (pinfunction "2_2") (pintype "passive"))
      (node (ref "C16") (pin "2") (pinfunction "2_2") (pintype "passive"))
      (node (ref "C2") (pin "2") (pinfunction "2_2") (pintype "passive"))
      (node (ref "C24") (pin "2") (pinfunction "2_2") (pintype "passive"))
      (node (ref "C25") (pin "2") (pinfunction "2_2") (pintype "passive"))
      (node (ref "C27") (pin "2") (pinfunction "2_2") (pintype "passive"))
      (node (ref "C28") (pin "2") (pinfunction "2_2") (pintype "passive"))
      (node (ref "C29") (pin "1") (pinfunction "1_1") (pintype "passive"))
      (node (ref "C3") (pin "2") (pinfunction "2_2") (pintype "passive"))
      (node (ref "C30") (pin "1") (pinfunction "1_1") (pintype "passive"))
      (node (ref "C31") (pin "2") (pinfunction "2_2") (pintype "passive"))
      (node (ref "C32") (pin "2") (pinfunction "2_2") (pintype "passive"))
      (node (ref "C34") (pin "2") (pinfunction "2_2") (pintype "passive"))
      (node (ref "C35") (pin "1") (pinfunction "1_1") (pintype "passive"))
      (node (ref "C36") (pin "2") (pinfunction "2_2") (pintype "passive"))
      (node (ref "C37") (pin "1") (pinfunction "1_1") (pintype "passive"))
      (node (ref "C38") (pin "2") (pinfunction "2_2") (pintype "passive"))
      (node (ref "C39") (pin "1") (pinfunction "1_1") (pintype "passive"))
      (node (ref "C4") (pin "2") (pinfunction "2_2") (pintype "passive"))
      (node (ref "C40") (pin "2") (pinfunction "2_2") (pintype "passive"))
      (node (ref "C41") (pin "1") (pinfunction "1_1") (pintype "passive"))
      (node (ref "C42") (pin "2") (pinfunction "2_2") (pintype "passive"))
      (node (ref "C43") (pin "1") (pinfunction "1_1") (pintype "passive"))
      (node (ref "C44") (pin "2") (pinfunction "2_2") (pintype "passive"))
      (node (ref "C45") (pin "1") (pinfunction "1_1") (pintype "passive"))
      (node (ref "C46") (pin "2") (pinfunction "2_2") (pintype "passive"))
      (node (ref "C47") (pin "1") (pinfunction "1_1") (pintype "passive"))
      (node (ref "C48") (pin "2") (pinfunction "2_2") (pintype "passive"))
      (node (ref "C49") (pin "1") (pinfunction "1_1") (pintype "passive"))
      (node (ref "C5") (pin "2") (pinfunction "2_2") (pintype "passive"))
      (node (ref "C50") (pin "2") (pinfunction "2_2") (pintype "passive"))
      (node (ref "C51") (pin "1") (pinfunction "1_1") (pintype "passive"))
      (node (ref "C52") (pin "1") (pinfunction "1_1") (pintype "passive"))
      (node (ref "C53") (pin "1") (pinfunction "1_1") (pintype "passive"))
      (node (ref "C54") (pin "1") (pinfunction "1_1") (pintype "passive"))
      (node (ref "C55") (pin "1") (pinfunction "1_1") (pintype "passive"))
      (node (ref "C56") (pin "1") (pinfunction "1_1") (pintype "passive"))
      (node (ref "C57") (pin "1") (pinfunction "1_1") (pintype "passive"))
      (node (ref "C58") (pin "1") (pinfunction "1_1") (pintype "passive"))
      (node (ref "C59") (pin "1") (pinfunction "1_1") (pintype "passive"))
      (node (ref "C6") (pin "2") (pinfunction "2_2") (pintype "passive"))
      (node (ref "C60") (pin "2") (pinfunction "2_2") (pintype "passive"))
      (node (ref "C61") (pin "1") (pinfunction "1_1") (pintype "passive"))
      (node (ref "C62") (pin "2") (pinfunction "2_2") (pintype "passive"))
      (node (ref "C63") (pin "2") (pinfunction "2_2") (pintype "passive"))
      (node (ref "C64") (pin "2") (pinfunction "2_2") (pintype "passive"))
      (node (ref "C65") (pin "2") (pinfunction "2_2") (pintype "passive"))
      (node (ref "C68") (pin "2") (pinfunction "2_2") (pintype "passive"))
      (node (ref "C70") (pin "1") (pinfunction "1_1") (pintype "passive"))
      (node (ref "C71") (pin "1") (pinfunction "1_1") (pintype "passive"))
      (node (ref "C72") (pin "1") (pinfunction "1_1") (pintype "passive"))
      (node (ref "C73") (pin "1") (pinfunction "1_1") (pintype "passive"))
      (node (ref "C9") (pin "2") (pinfunction "2_2") (pintype "passive"))
      (node (ref "D1") (pin "C") (pinfunction "C_C") (pintype "passive"))
      (node (ref "D2") (pin "C") (pinfunction "C_C") (pintype "passive"))
      (node (ref "IC1") (pin "33") (pinfunction "DGND_33") (pintype "power_in"))
      (node (ref "IC1") (pin "41") (pinfunction "DAISY_IN_41") (pintype "input"))
      (node (ref "IC1") (pin "49") (pinfunction "DGND_49") (pintype "power_in"))
      (node (ref "IC1") (pin "51") (pinfunction "DGND_51") (pintype "power_in"))
      (node (ref "IC10") (pin "11") (pinfunction "GND_11") (pintype "bidirectional"))
      (node (ref "IC10") (pin "12") (pinfunction "B8_12") (pintype "bidirectional"))
      (node (ref "IC10") (pin "13") (pinfunction "B7_13") (pintype "bidirectional"))
      (node (ref "IC10") (pin "8") (pinfunction "A7_8") (pintype "bidirectional"))
      (node (ref "IC10") (pin "9") (pinfunction "A8_9") (pintype "bidirectional"))
      (node (ref "IC11") (pin "11") (pinfunction "GND_11") (pintype "bidirectional"))
      (node (ref "IC11") (pin "12") (pinfunction "B8_12") (pintype "bidirectional"))
      (node (ref "IC11") (pin "13") (pinfunction "B7_13") (pintype "bidirectional"))
      (node (ref "IC11") (pin "16") (pinfunction "B4_16") (pintype "bidirectional"))
      (node (ref "IC11") (pin "17") (pinfunction "B3_17") (pintype "bidirectional"))
      (node (ref "IC11") (pin "4") (pinfunction "A3_4") (pintype "bidirectional"))
      (node (ref "IC11") (pin "5") (pinfunction "A4_5") (pintype "bidirectional"))
      (node (ref "IC11") (pin "8") (pinfunction "A7_8") (pintype "bidirectional"))
      (node (ref "IC11") (pin "9") (pinfunction "A8_9") (pintype "bidirectional"))
      (node (ref "IC2") (pin "1") (pinfunction "GND_1") (pintype "bidirectional"))
      (node (ref "IC3") (pin "2") (pinfunction "GND_2") (pintype "bidirectional"))
      (node (ref "IC5") (pin "4") (pinfunction "GND_4") (pintype "power_in"))
      (node (ref "IC5") (pin "7") (pinfunction "WP_7") (pintype "input"))
      (node (ref "IC6") (pin "4") (pinfunction "GND_4") (pintype "bidirectional"))
      (node (ref "IC9") (pin "P$2") (pinfunction "GND_P$2") (pintype "bidirectional"))
      (node (ref "JP15") (pin "4") (pinfunction "4_4") (pintype "passive"))
      (node (ref "JP16") (pin "4") (pinfunction "4_4") (pintype "passive"))
      (node (ref "JP16") (pin "5") (pinfunction "5_5") (pintype "passive"))
      (node (ref "JP16") (pin "6") (pinfunction "6_6") (pintype "passive"))
      (node (ref "JP23") (pin "35") (pinfunction "35_35") (pintype "passive"))
      (node (ref "JP23") (pin "36") (pinfunction "36_36") (pintype "passive"))
      (node (ref "JP5") (pin "3") (pinfunction "3_3") (pintype "passive"))
      (node (ref "R19") (pin "1") (pinfunction "1_1") (pintype "passive"))
      (node (ref "R20") (pin "1") (pinfunction "1_1") (pintype "passive"))
      (node (ref "R21") (pin "1") (pinfunction "1_1") (pintype "passive"))
      (node (ref "SPI") (pin "6") (pinfunction "6_6") (pintype "passive"))
      (node (ref "TP3") (pin "1") (pinfunction "1_1") (pintype "passive"))
    )
    (net (code "19") (name "AIN1N") (class "Default")
      (node (ref "C35") (pin "2") (pinfunction "2_2") (pintype "passive"))
      (node (ref "IC1") (pin "15") (pinfunction "IN1N_15") (pintype "input"))
      (node (ref "R35") (pin "2") (pinfunction "2_2") (pintype "passive"))
    )
    (net (code "20") (name "AIN1P") (class "Default")
      (node (ref "C34") (pin "1") (pinfunction "1_1") (pintype "passive"))
      (node (ref "IC1") (pin "16") (pinfunction "IN1P_16") (pintype "input"))
      (node (ref "R34") (pin "2") (pinfunction "2_2") (pintype "passive"))
    )
    (net (code "21") (name "AIN2N") (class "Default")
      (node (ref "C37") (pin "2") (pinfunction "2_2") (pintype "passive"))
      (node (ref "IC1") (pin "13") (pinfunction "IN2N_13") (pintype "input"))
      (node (ref "R37") (pin "2") (pinfunction "2_2") (pintype "passive"))
    )
    (net (code "22") (name "AIN2P") (class "Default")
      (node (ref "C36") (pin "1") (pinfunction "1_1") (pintype "passive"))
      (node (ref "IC1") (pin "14") (pinfunction "IN2P_14") (pintype "input"))
      (node (ref "R36") (pin "2") (pinfunction "2_2") (pintype "passive"))
    )
    (net (code "23") (name "AIN3N") (class "Default")
      (node (ref "C39") (pin "2") (pinfunction "2_2") (pintype "passive"))
      (node (ref "IC1") (pin "11") (pinfunction "IN3N_11") (pintype "input"))
      (node (ref "R39") (pin "2") (pinfunction "2_2") (pintype "passive"))
    )
    (net (code "24") (name "AIN3P") (class "Default")
      (node (ref "C38") (pin "1") (pinfunction "1_1") (pintype "passive"))
      (node (ref "IC1") (pin "12") (pinfunction "IN3P_12") (pintype "input"))
      (node (ref "R38") (pin "2") (pinfunction "2_2") (pintype "passive"))
    )
    (net (code "25") (name "AIN4N") (class "Default")
      (node (ref "C41") (pin "2") (pinfunction "2_2") (pintype "passive"))
      (node (ref "IC1") (pin "9") (pinfunction "IN4N_9") (pintype "input"))
      (node (ref "R41") (pin "2") (pinfunction "2_2") (pintype "passive"))
    )
    (net (code "26") (name "AIN4P") (class "Default")
      (node (ref "C40") (pin "1") (pinfunction "1_1") (pintype "passive"))
      (node (ref "IC1") (pin "10") (pinfunction "IN4P_10") (pintype "input"))
      (node (ref "R40") (pin "2") (pinfunction "2_2") (pintype "passive"))
    )
    (net (code "27") (name "AIN5N") (class "Default")
      (node (ref "C43") (pin "2") (pinfunction "2_2") (pintype "passive"))
      (node (ref "IC1") (pin "7") (pinfunction "IN5N_7") (pintype "input"))
      (node (ref "R43") (pin "2") (pinfunction "2_2") (pintype "passive"))
    )
    (net (code "28") (name "AIN5P") (class "Default")
      (node (ref "C42") (pin "1") (pinfunction "1_1") (pintype "passive"))
      (node (ref "IC1") (pin "8") (pinfunction "IN5P_8") (pintype "input"))
      (node (ref "R42") (pin "2") (pinfunction "2_2") (pintype "passive"))
    )
    (net (code "29") (name "AIN6N") (class "Default")
      (node (ref "C45") (pin "2") (pinfunction "2_2") (pintype "passive"))
      (node (ref "IC1") (pin "5") (pinfunction "IN6N_5") (pintype "input"))
      (node (ref "R45") (pin "2") (pinfunction "2_2") (pintype "passive"))
    )
    (net (code "30") (name "AIN6P") (class "Default")
      (node (ref "C44") (pin "1") (pinfunction "1_1") (pintype "passive"))
      (node (ref "IC1") (pin "6") (pinfunction "IN6P_6") (pintype "input"))
      (node (ref "R44") (pin "2") (pinfunction "2_2") (pintype "passive"))
    )
    (net (code "31") (name "AIN7N") (class "Default")
      (node (ref "C47") (pin "2") (pinfunction "2_2") (pintype "passive"))
      (node (ref "IC1") (pin "3") (pinfunction "IN7N_3") (pintype "input"))
      (node (ref "R47") (pin "2") (pinfunction "2_2") (pintype "passive"))
    )
    (net (code "32") (name "AIN7P") (class "Default")
      (node (ref "C46") (pin "1") (pinfunction "1_1") (pintype "passive"))
      (node (ref "IC1") (pin "4") (pinfunction "IN7P_4") (pintype "input"))
      (node (ref "R46") (pin "2") (pinfunction "2_2") (pintype "passive"))
    )
    (net (code "33") (name "AIN8N") (class "Default")
      (node (ref "C49") (pin "2") (pinfunction "2_2") (pintype "passive"))
      (node (ref "IC1") (pin "1") (pinfunction "IN8N_1") (pintype "input"))
      (node (ref "R49") (pin "2") (pinfunction "2_2") (pintype "passive"))
    )
    (net (code "34") (name "AIN8P") (class "Default")
      (node (ref "C48") (pin "1") (pinfunction "1_1") (pintype "passive"))
      (node (ref "IC1") (pin "2") (pinfunction "IN8P_2") (pintype "input"))
      (node (ref "R48") (pin "2") (pinfunction "2_2") (pintype "passive"))
    )
    (net (code "35") (name "ARD_SCL") (class "Default")
      (node (ref "IC9") (pin "P$1") (pinfunction "B2_P$1") (pintype "bidirectional"))
      (node (ref "JP22") (pin "8") (pinfunction "8_8") (pintype "passive"))
    )
    (net (code "36") (name "ARD_SDA") (class "Default")
      (node (ref "IC9") (pin "P$8") (pinfunction "B1_P$8") (pintype "bidirectional"))
      (node (ref "JP22") (pin "7") (pinfunction "7_7") (pintype "passive"))
    )
    (net (code "37") (name "AVDD") (class "Default")
      (node (ref "C10") (pin "1") (pinfunction "1_1") (pintype "passive"))
      (node (ref "C11") (pin "1") (pinfunction "1_1") (pintype "passive"))
      (node (ref "C12") (pin "1") (pinfunction "1_1") (pintype "passive"))
      (node (ref "C33") (pin "1") (pinfunction "1_1") (pintype "passive"))
      (node (ref "C50") (pin "1") (pinfunction "1_1") (pintype "passive"))
      (node (ref "C60") (pin "1") (pinfunction "1_1") (pintype "passive"))
      (node (ref "C7") (pin "1") (pinfunction "1_1") (pintype "passive"))
      (node (ref "C8") (pin "1") (pinfunction "1_1") (pintype "passive"))
      (node (ref "C9") (pin "1") (pinfunction "1_1") (pintype "passive"))
      (node (ref "IC1") (pin "19") (pinfunction "AVDD_19") (pintype "power_in"))
      (node (ref "IC1") (pin "21") (pinfunction "AVDD_21") (pintype "power_in"))
      (node (ref "IC1") (pin "22") (pinfunction "AVDD_22") (pintype "power_in"))
      (node (ref "IC1") (pin "54") (pinfunction "AVDD_54") (pintype "power_in"))
      (node (ref "IC1") (pin "56") (pinfunction "AVDD_56") (pintype "power_in"))
      (node (ref "IC1") (pin "59") (pinfunction "AVDD_59") (pintype "power_in"))
      (node (ref "IC7") (pin "5") (pinfunction "V_P_5") (pintype "bidirectional"))
      (node (ref "IC8") (pin "5") (pinfunction "V_P_5") (pintype "bidirectional"))
      (node (ref "JP16") (pin "2") (pinfunction "2_2") (pintype "passive"))
      (node (ref "JP4") (pin "2") (pinfunction "2_2") (pintype "passive"))
      (node (ref "R23") (pin "1") (pinfunction "1_1") (pintype "passive"))
      (node (ref "TP1") (pin "1") (pinfunction "1_1") (pintype "passive"))
    )
    (net (code "38") (name "AVSS") (class "Default")
      (node (ref "C11") (pin "2") (pinfunction "2_2") (pintype "passive"))
      (node (ref "C12") (pin "2") (pinfunction "2_2") (pintype "passive"))
      (node (ref "C17") (pin "2") (pinfunction "2_2") (pintype "passive"))
      (node (ref "C18") (pin "2") (pinfunction "2_2") (pintype "passive"))
      (node (ref "C19") (pin "2") (pinfunction "2_2") (pintype "passive"))
      (node (ref "C20") (pin "2") (pinfunction "2_2") (pintype "passive"))
      (node (ref "C21") (pin "2") (pinfunction "2_2") (pintype "passive"))
      (node (ref "C22") (pin "2") (pinfunction "2_2") (pintype "passive"))
      (node (ref "C23") (pin "2") (pinfunction "2_2") (pintype "passive"))
      (node (ref "C29") (pin "2") (pinfunction "2_2") (pintype "passive"))
      (node (ref "C30") (pin "2") (pinfunction "2_2") (pintype "passive"))
      (node (ref "C33") (pin "2") (pinfunction "2_2") (pintype "passive"))
      (node (ref "C51") (pin "2") (pinfunction "2_2") (pintype "passive"))
      (node (ref "C61") (pin "2") (pinfunction "2_2") (pintype "passive"))
      (node (ref "C7") (pin "2") (pinfunction "2_2") (pintype "passive"))
      (node (ref "C8") (pin "2") (pinfunction "2_2") (pintype "passive"))
      (node (ref "IC1") (pin "20") (pinfunction "AVSS_20") (pintype "power_in"))
      (node (ref "IC1") (pin "23") (pinfunction "AVSS_23") (pintype "power_in"))
      (node (ref "IC1") (pin "25") (pinfunction "VREFN_25") (pintype "bidirectional"))
      (node (ref "IC1") (pin "32") (pinfunction "AVSS_32") (pintype "power_in"))
      (node (ref "IC1") (pin "53") (pinfunction "AVSS1_53") (pintype "power_in"))
      (node (ref "IC1") (pin "57") (pinfunction "AVSS_57") (pintype "power_in"))
      (node (ref "IC1") (pin "58") (pinfunction "AVSS_58") (pintype "power_in"))
      (node (ref "IC7") (pin "2") (pinfunction "V_N_2") (pintype "bidirectional"))
      (node (ref "IC8") (pin "2") (pinfunction "V_N_2") (pintype "bidirectional"))
      (node (ref "JP5") (pin "2") (pinfunction "2_2") (pintype "passive"))
      (node (ref "R22") (pin "2") (pinfunction "2_2") (pintype "passive"))
      (node (ref "TP2") (pin "1") (pinfunction "1_1") (pintype "passive"))
    )
    (net (code "39") (name "BIASIN") (class "Default")
      (node (ref "IC1") (pin "62") (pinfunction "BIASIN_62") (pintype "input"))
      (node (ref "JP9") (pin "3") (pinfunction "3_3") (pintype "passive"))
    )
    (net (code "40") (name "BIASINV") (class "Default")
      (node (ref "C66") (pin "2") (pinfunction "2_2") (pintype "passive"))
      (node (ref "IC1") (pin "61") (pinfunction "BIASINV_61") (pintype "bidirectional"))
      (node (ref "JP15") (pin "1") (pinfunction "1_1") (pintype "passive"))
      (node (ref "JP16") (pin "3") (pinfunction "3_3") (pintype "passive"))
      (node (ref "R6") (pin "1") (pinfunction "1_1") (pintype "passive"))
    )
    (net (code "41") (name "BIASOUT") (class "Default")
      (node (ref "C66") (pin "1") (pinfunction "1_1") (pintype "passive"))
      (node (ref "IC1") (pin "63") (pinfunction "BIASOUT_63") (pintype "output"))
      (node (ref "JP9") (pin "2") (pinfunction "2_2") (pintype "passive"))
      (node (ref "R6") (pin "2") (pinfunction "2_2") (pintype "passive"))
    )
    (net (code "42") (name "BIAS_ELEC") (class "Default")
      (node (ref "JP6") (pin "1") (pinfunction "1_1") (pintype "passive"))
      (node (ref "JP9") (pin "1") (pinfunction "1_1") (pintype "passive"))
      (node (ref "R24") (pin "2") (pinfunction "2_2") (pintype "passive"))
    )
    (net (code "43") (name "BIAS_ELEC_CON") (class "Default")
      (node (ref "JP16") (pin "24") (pinfunction "24_24") (pintype "passive"))
      (node (ref "R24") (pin "1") (pinfunction "1_1") (pintype "passive"))
    )
    (net (code "44") (name "BOARD_ADDR_0") (class "Default")
      (node (ref "IC1") (pin "42") (pinfunction "GPIO1_42") (pintype "bidirectional"))
      (node (ref "IC5") (pin "1") (pinfunction "A0_1") (pintype "input"))
      (node (ref "JP3") (pin "3") (pinfunction "3_3") (pintype "passive"))
      (node (ref "R19") (pin "2") (pinfunction "2_2") (pintype "passive"))
    )
    (net (code "45") (name "BOARD_ADDR_1") (class "Default")
      (node (ref "IC1") (pin "44") (pinfunction "GPIO2_44") (pintype "bidirectional"))
      (node (ref "IC5") (pin "2") (pinfunction "A1_2") (pintype "input"))
      (node (ref "JP3") (pin "1") (pinfunction "1_1") (pintype "passive"))
      (node (ref "R20") (pin "2") (pinfunction "2_2") (pintype "passive"))
    )
    (net (code "46") (name "BOARD_ADDR_2") (class "Default")
      (node (ref "IC1") (pin "45") (pinfunction "GPIO3_45") (pintype "bidirectional"))
      (node (ref "IC5") (pin "3") (pinfunction "A2_3") (pintype "input"))
      (node (ref "R21") (pin "2") (pinfunction "2_2") (pintype "passive"))
    )
    (net (code "47") (name "CLK") (class "Default")
      (node (ref "IC1") (pin "37") (pinfunction "CLK_37") (pintype "input"))
      (node (ref "IC10") (pin "6") (pinfunction "A5_6") (pintype "bidirectional"))
    )
    (net (code "48") (name "CLKSEL") (class "Default")
      (node (ref "IC1") (pin "52") (pinfunction "CLKSEL_52") (pintype "input"))
      (node (ref "IC10") (pin "1") (pinfunction "A1_1") (pintype "bidirectional"))
    )
    (net (code "49") (name "DRDY") (class "Default")
      (node (ref "IC1") (pin "47") (pinfunction "~{DRDY}_47") (pintype "output"))
      (node (ref "IC10") (pin "3") (pinfunction "A2_3") (pintype "bidirectional"))
    )
    (net (code "50") (name "DVDD") (class "Default")
      (node (ref "C13") (pin "1") (pinfunction "1_1") (pintype "passive"))
      (node (ref "C14") (pin "1") (pinfunction "1_1") (pintype "passive"))
      (node (ref "C25") (pin "1") (pinfunction "1_1") (pintype "passive"))
      (node (ref "C52") (pin "2") (pinfunction "2_2") (pintype "passive"))
      (node (ref "C53") (pin "2") (pinfunction "2_2") (pintype "passive"))
      (node (ref "C56") (pin "2") (pinfunction "2_2") (pintype "passive"))
      (node (ref "C57") (pin "2") (pinfunction "2_2") (pintype "passive"))
      (node (ref "C63") (pin "1") (pinfunction "1_1") (pintype "passive"))
      (node (ref "C70") (pin "2") (pinfunction "2_2") (pintype "passive"))
      (node (ref "C71") (pin "2") (pinfunction "2_2") (pintype "passive"))
      (node (ref "IC1") (pin "48") (pinfunction "DVDD_48") (pintype "power_in"))
      (node (ref "IC1") (pin "50") (pinfunction "DVDD_50") (pintype "power_in"))
      (node (ref "IC10") (pin "2") (pinfunction "VCCA_2") (pintype "bidirectional"))
      (node (ref "IC11") (pin "2") (pinfunction "VCCA_2") (pintype "bidirectional"))
      (node (ref "IC5") (pin "8") (pinfunction "VCC_8") (pintype "power_in"))
      (node (ref "IC9") (pin "P$3") (pinfunction "VCCA_P$3") (pintype "bidirectional"))
      (node (ref "JP16") (pin "1") (pinfunction "1_1") (pintype "passive"))
      (node (ref "JP26") (pin "4") (pinfunction "4_4") (pintype "passive"))
      (node (ref "JP3") (pin "2") (pinfunction "2_2") (pintype "passive"))
      (node (ref "JP3") (pin "4") (pinfunction "4_4") (pintype "passive"))
      (node (ref "R1") (pin "1") (pinfunction "1_1") (pintype "passive"))
      (node (ref "R2") (pin "1") (pinfunction "1_1") (pintype "passive"))
      (node (ref "R3") (pin "1") (pinfunction "1_1") (pintype "passive"))
      (node (ref "R4") (pin "1") (pinfunction "1_1") (pintype "passive"))
    )
    (net (code "51") (name "GPIO4") (class "Default")
      (node (ref "IC1") (pin "46") (pinfunction "GPIO4_46") (pintype "bidirectional"))
      (node (ref "R18") (pin "1") (pinfunction "1_1") (pintype "passive"))
    )
    (net (code "52") (name "IN1N") (class "Default")
      (node (ref "JP16") (pin "8") (pinfunction "8_8") (pintype "passive"))
      (node (ref "R35") (pin "1") (pinfunction "1_1") (pintype "passive"))
    )
    (net (code "53") (name "IN1P") (class "Default")
      (node (ref "JP16") (pin "7") (pinfunction "7_7") (pintype "passive"))
      (node (ref "R34") (pin "1") (pinfunction "1_1") (pintype "passive"))
    )
    (net (code "54") (name "IN2N") (class "Default")
      (node (ref "JP16") (pin "10") (pinfunction "10_10") (pintype "passive"))
      (node (ref "R37") (pin "1") (pinfunction "1_1") (pintype "passive"))
    )
    (net (code "55") (name "IN2P") (class "Default")
      (node (ref "JP16") (pin "9") (pinfunction "9_9") (pintype "passive"))
      (node (ref "R36") (pin "1") (pinfunction "1_1") (pintype "passive"))
    )
    (net (code "56") (name "IN3N") (class "Default")
      (node (ref "JP16") (pin "12") (pinfunction "12_12") (pintype "passive"))
      (node (ref "R39") (pin "1") (pinfunction "1_1") (pintype "passive"))
    )
    (net (code "57") (name "IN3P") (class "Default")
      (node (ref "JP16") (pin "11") (pinfunction "11_11") (pintype "passive"))
      (node (ref "R38") (pin "1") (pinfunction "1_1") (pintype "passive"))
    )
    (net (code "58") (name "IN4N") (class "Default")
      (node (ref "JP16") (pin "14") (pinfunction "14_14") (pintype "passive"))
      (node (ref "R41") (pin "1") (pinfunction "1_1") (pintype "passive"))
    )
    (net (code "59") (name "IN4P") (class "Default")
      (node (ref "JP16") (pin "13") (pinfunction "13_13") (pintype "passive"))
      (node (ref "R40") (pin "1") (pinfunction "1_1") (pintype "passive"))
    )
    (net (code "60") (name "IN5N") (class "Default")
      (node (ref "JP16") (pin "16") (pinfunction "16_16") (pintype "passive"))
      (node (ref "R43") (pin "1") (pinfunction "1_1") (pintype "passive"))
    )
    (net (code "61") (name "IN5P") (class "Default")
      (node (ref "JP16") (pin "15") (pinfunction "15_15") (pintype "passive"))
      (node (ref "R42") (pin "1") (pinfunction "1_1") (pintype "passive"))
    )
    (net (code "62") (name "IN6N") (class "Default")
      (node (ref "JP16") (pin "18") (pinfunction "18_18") (pintype "passive"))
      (node (ref "R45") (pin "1") (pinfunction "1_1") (pintype "passive"))
    )
    (net (code "63") (name "IN6P") (class "Default")
      (node (ref "JP16") (pin "17") (pinfunction "17_17") (pintype "passive"))
      (node (ref "R44") (pin "1") (pinfunction "1_1") (pintype "passive"))
    )
    (net (code "64") (name "IN7N") (class "Default")
      (node (ref "JP16") (pin "20") (pinfunction "20_20") (pintype "passive"))
      (node (ref "R47") (pin "1") (pinfunction "1_1") (pintype "passive"))
    )
    (net (code "65") (name "IN7P") (class "Default")
      (node (ref "JP16") (pin "19") (pinfunction "19_19") (pintype "passive"))
      (node (ref "R46") (pin "1") (pinfunction "1_1") (pintype "passive"))
    )
    (net (code "66") (name "IN8N") (class "Default")
      (node (ref "JP16") (pin "22") (pinfunction "22_22") (pintype "passive"))
      (node (ref "R49") (pin "1") (pinfunction "1_1") (pintype "passive"))
    )
    (net (code "67") (name "IN8P") (class "Default")
      (node (ref "JP16") (pin "21") (pinfunction "21_21") (pintype "passive"))
      (node (ref "R48") (pin "1") (pinfunction "1_1") (pintype "passive"))
    )
    (net (code "68") (name "IOREF") (class "Default")
      (node (ref "C54") (pin "2") (pinfunction "2_2") (pintype "passive"))
      (node (ref "C55") (pin "2") (pinfunction "2_2") (pintype "passive"))
      (node (ref "C58") (pin "2") (pinfunction "2_2") (pintype "passive"))
      (node (ref "C59") (pin "2") (pinfunction "2_2") (pintype "passive"))
      (node (ref "C72") (pin "2") (pinfunction "2_2") (pintype "passive"))
      (node (ref "C73") (pin "2") (pinfunction "2_2") (pintype "passive"))
      (node (ref "IC10") (pin "19") (pinfunction "VCCB_19") (pintype "bidirectional"))
      (node (ref "IC11") (pin "19") (pinfunction "VCCB_19") (pintype "bidirectional"))
      (node (ref "IC9") (pin "P$7") (pinfunction "VCCB_P$7") (pintype "bidirectional"))
      (node (ref "JP26") (pin "2") (pinfunction "2_2") (pintype "passive"))
    )
    (net (code "69") (name "Net-(D1-PadA)") (class "Default")
      (node (ref "D1") (pin "A") (pinfunction "A_A") (pintype "passive"))
      (node (ref "R1") (pin "2") (pinfunction "2_2") (pintype "passive"))
    )
    (net (code "70") (name "Net-(D2-PadA)") (class "Default")
      (node (ref "D2") (pin "A") (pinfunction "A_A") (pintype "passive"))
      (node (ref "R18") (pin "2") (pinfunction "2_2") (pintype "passive"))
    )
    (net (code "71") (name "Net-(IC1-VCAP1)") (class "Default")
      (node (ref "C17") (pin "1") (pinfunction "1_1") (pintype "passive"))
      (node (ref "IC1") (pin "28") (pinfunction "VCAP1_28") (pintype "bidirectional"))
    )
    (net (code "72") (name "Net-(IC1-VCAP2)") (class "Default")
      (node (ref "C18") (pin "1") (pinfunction "1_1") (pintype "passive"))
      (node (ref "IC1") (pin "30") (pinfunction "VCAP2_30") (pintype "bidirectional"))
    )
    (net (code "73") (name "Net-(IC1-VCAP3)") (class "Default")
      (node (ref "C19") (pin "1") (pinfunction "1_1") (pintype "passive"))
      (node (ref "C20") (pin "1") (pinfunction "1_1") (pintype "passive"))
      (node (ref "IC1") (pin "55") (pinfunction "VCAP3_55") (pintype "bidirectional"))
    )
    (net (code "74") (name "Net-(IC1-VCAP4)") (class "Default")
      (node (ref "C21") (pin "1") (pinfunction "1_1") (pintype "passive"))
      (node (ref "IC1") (pin "26") (pinfunction "VCAP4_26") (pintype "bidirectional"))
    )
    (net (code "75") (name "Net-(IC2-NR{slash}FB)") (class "Default")
      (node (ref "C31") (pin "1") (pinfunction "1_1") (pintype "passive"))
      (node (ref "IC2") (pin "4") (pinfunction "NR/FB_4") (pintype "bidirectional"))
    )
    (net (code "76") (name "Net-(IC2-OUT)") (class "Default")
      (node (ref "C1") (pin "1") (pinfunction "1_1") (pintype "passive"))
      (node (ref "C2") (pin "1") (pinfunction "1_1") (pintype "passive"))
      (node (ref "IC2") (pin "5") (pinfunction "OUT_5") (pintype "bidirectional"))
      (node (ref "L1") (pin "1") (pinfunction "1_1") (pintype "passive"))
    )
    (net (code "77") (name "Net-(IC3-NR{slash}FB)") (class "Default")
      (node (ref "C32") (pin "1") (pinfunction "1_1") (pintype "passive"))
      (node (ref "IC3") (pin "4") (pinfunction "NR/FB_4") (pintype "bidirectional"))
    )
    (net (code "78") (name "Net-(IC3-OUT)") (class "Default")
      (node (ref "C4") (pin "1") (pinfunction "1_1") (pintype "passive"))
      (node (ref "C5") (pin "1") (pinfunction "1_1") (pintype "passive"))
      (node (ref "IC3") (pin "5") (pinfunction "OUT_5") (pintype "bidirectional"))
      (node (ref "L2") (pin "1") (pinfunction "1_1") (pintype "passive"))
    )
    (net (code "79") (name "Net-(IC6-CFLY_N)") (class "Default")
      (node (ref "C26") (pin "1") (pinfunction "1_1") (pintype "passive"))
      (node (ref "IC6") (pin "3") (pinfunction "CFLY_N_3") (pintype "bidirectional"))
    )
    (net (code "80") (name "Net-(IC6-CFLY_P)") (class "Default")
      (node (ref "C26") (pin "2") (pinfunction "2_2") (pintype "passive"))
      (node (ref "IC6") (pin "5") (pinfunction "CFLY_P_5") (pintype "bidirectional"))
    )
    (net (code "81") (name "Net-(IC6-OUT)") (class "Default")
      (node (ref "C15") (pin "1") (pinfunction "1_1") (pintype "passive"))
      (node (ref "C16") (pin "1") (pinfunction "1_1") (pintype "passive"))
      (node (ref "IC6") (pin "1") (pinfunction "OUT_1") (pintype "bidirectional"))
      (node (ref "L3") (pin "1") (pinfunction "1_1") (pintype "passive"))
    )
    (net (code "82") (name "Net-(IC7-N_IN)") (class "Default")
      (node (ref "IC7") (pin "1") (pinfunction "OUT_1") (pintype "bidirectional"))
      (node (ref "IC7") (pin "4") (pinfunction "N_IN_4") (pintype "bidirectional"))
      (node (ref "JP6") (pin "3") (pinfunction "3_3") (pintype "passive"))
    )
    (net (code "83") (name "Net-(IC7-P_IN)") (class "Default")
      (node (ref "IC7") (pin "3") (pinfunction "P_IN_3") (pintype "bidirectional"))
      (node (ref "R22") (pin "1") (pinfunction "1_1") (pintype "passive"))
      (node (ref "R23") (pin "2") (pinfunction "2_2") (pintype "passive"))
    )
    (net (code "84") (name "Net-(IC8-N_IN)") (class "Default")
      (node (ref "IC8") (pin "1") (pinfunction "OUT_1") (pintype "bidirectional"))
      (node (ref "IC8") (pin "4") (pinfunction "N_IN_4") (pintype "bidirectional"))
      (node (ref "JP8") (pin "3") (pinfunction "3_3") (pintype "passive"))
    )
    (net (code "85") (name "Net-(IC8-P_IN)") (class "Default")
      (node (ref "IC8") (pin "3") (pinfunction "P_IN_3") (pintype "bidirectional"))
      (node (ref "JP7") (pin "2") (pinfunction "2_2") (pintype "passive"))
    )
    (net (code "86") (name "Net-(IC9-OE)") (class "Default")
      (node (ref "IC9") (pin "P$6") (pinfunction "OE_P$6") (pintype "bidirectional"))
      (node (ref "R4") (pin "2") (pinfunction "2_2") (pintype "passive"))
    )
    (net (code "87") (name "Net-(IC10-OE)") (class "Default")
      (node (ref "IC10") (pin "10") (pinfunction "OE_10") (pintype "bidirectional"))
      (node (ref "R2") (pin "2") (pinfunction "2_2") (pintype "passive"))
    )
    (net (code "88") (name "Net-(IC11-OE)") (class "Default")
      (node (ref "IC11") (pin "10") (pinfunction "OE_10") (pintype "bidirectional"))
      (node (ref "R3") (pin "2") (pinfunction "2_2") (pintype "passive"))
    )
    (net (code "89") (name "REF_ELEC") (class "Default")
      (node (ref "C62") (pin "1") (pinfunction "1_1") (pintype "passive"))
      (node (ref "JP7") (pin "1") (pinfunction "1_1") (pintype "passive"))
      (node (ref "JP8") (pin "1") (pinfunction "1_1") (pintype "passive"))
      (node (ref "R25") (pin "1") (pinfunction "1_1") (pintype "passive"))
    )
    (net (code "90") (name "REF_ELEC_CON") (class "Default")
      (node (ref "JP16") (pin "23") (pinfunction "23_23") (pintype "passive"))
      (node (ref "R25") (pin "2") (pinfunction "2_2") (pintype "passive"))
    )
    (net (code "91") (name "RESET") (class "Default")
      (node (ref "SPI") (pin "5") (pinfunction "5_5") (pintype "passive"))
    )
    (net (code "92") (name "SCL") (class "Default")
      (node (ref "IC5") (pin "6") (pinfunction "SCL_6") (pintype "input"))
      (node (ref "IC9") (pin "P$4") (pinfunction "A2_P$4") (pintype "bidirectional"))
    )
    (net (code "93") (name "SDA") (class "Default")
      (node (ref "IC5") (pin "5") (pinfunction "SDA_5") (pintype "bidirectional"))
      (node (ref "IC9") (pin "P$5") (pinfunction "A1_P$5") (pintype "bidirectional"))
    )
    (net (code "94") (name "SPI0_MISO") (class "Default")
      (node (ref "JP2") (pin "2") (pinfunction "2_2") (pintype "passive"))
      (node (ref "SPI") (pin "1") (pinfunction "1_1") (pintype "passive"))
    )
    (net (code "95") (name "SPI0_MOSI") (class "Default")
      (node (ref "JP2") (pin "18") (pinfunction "18_18") (pintype "passive"))
      (node (ref "SPI") (pin "4") (pinfunction "4_4") (pintype "passive"))
    )
    (net (code "96") (name "SPI0_SCK") (class "Default")
      (node (ref "JP2") (pin "8") (pinfunction "8_8") (pintype "passive"))
      (node (ref "SPI") (pin "3") (pinfunction "3_3") (pintype "passive"))
    )
    (net (code "97") (name "SPI_CLK") (class "Default")
      (node (ref "IC1") (pin "40") (pinfunction "SCLK_40") (pintype "input"))
      (node (ref "IC10") (pin "5") (pinfunction "A4_5") (pintype "bidirectional"))
    )
    (net (code "98") (name "SPI_IN") (class "Default")
      (node (ref "IC1") (pin "34") (pinfunction "DIN_34") (pintype "input"))
      (node (ref "IC10") (pin "7") (pinfunction "A6_7") (pintype "bidirectional"))
    )
    (net (code "99") (name "SPI_OUT") (class "Default")
      (node (ref "IC1") (pin "43") (pinfunction "DOUT_43") (pintype "output"))
      (node (ref "IC10") (pin "4") (pinfunction "A3_4") (pintype "bidirectional"))
    )
    (net (code "100") (name "SRB1") (class "Default")
      (node (ref "IC1") (pin "18") (pinfunction "SRB2_18") (pintype "output"))
      (node (ref "JP6") (pin "2") (pinfunction "2_2") (pintype "passive"))
      (node (ref "JP8") (pin "2") (pinfunction "2_2") (pintype "passive"))
    )
    (net (code "101") (name "SRB2") (class "Default")
      (node (ref "IC1") (pin "17") (pinfunction "SRB1_17") (pintype "output"))
      (node (ref "JP7") (pin "3") (pinfunction "3_3") (pintype "passive"))
    )
    (net (code "102") (name "START") (class "Default")
      (node (ref "IC1") (pin "38") (pinfunction "START_38") (pintype "input"))
      (node (ref "IC11") (pin "3") (pinfunction "A2_3") (pintype "bidirectional"))
    )
    (net (code "103") (name "USART1_MISO") (class "Default")
      (node (ref "JP2") (pin "4") (pinfunction "4_4") (pintype "passive"))
      (node (ref "JP22") (pin "4") (pinfunction "4_4") (pintype "passive"))
    )
    (net (code "104") (name "USART1_MOSI") (class "Default")
      (node (ref "JP2") (pin "20") (pinfunction "20_20") (pintype "passive"))
      (node (ref "JP22") (pin "3") (pinfunction "3_3") (pintype "passive"))
    )
    (net (code "105") (name "USART1_SCK") (class "Default")
      (node (ref "JP2") (pin "6") (pinfunction "6_6") (pintype "passive"))
      (node (ref "JP25") (pin "1") (pinfunction "1_1") (pintype "passive"))
    )
    (net (code "106") (name "VCC_-5V") (class "Default")
      (node (ref "C24") (pin "1") (pinfunction "1_1") (pintype "passive"))
      (node (ref "C28") (pin "1") (pinfunction "1_1") (pintype "passive"))
      (node (ref "IC2") (pin "2") (pinfunction "IN_2") (pintype "bidirectional"))
      (node (ref "IC2") (pin "3") (pinfunction "EN_3") (pintype "bidirectional"))
      (node (ref "L3") (pin "2") (pinfunction "2_2") (pintype "passive"))
    )
    (net (code "107") (name "VCC_5V") (class "Default")
      (node (ref "C27") (pin "1") (pinfunction "1_1") (pintype "passive"))
      (node (ref "L4") (pin "1") (pinfunction "1_1") (pintype "passive"))
      (node (ref "SPI") (pin "2") (pinfunction "2_2") (pintype "passive"))
    )
    (net (code "108") (name "VCC_5V_FILTERED") (class "Default")
      (node (ref "C64") (pin "1") (pinfunction "1_1") (pintype "passive"))
      (node (ref "C65") (pin "1") (pinfunction "1_1") (pintype "passive"))
      (node (ref "C68") (pin "1") (pinfunction "1_1") (pintype "passive"))
      (node (ref "IC3") (pin "1") (pinfunction "IN_1") (pintype "bidirectional"))
      (node (ref "IC3") (pin "3") (pinfunction "EN_3") (pintype "bidirectional"))
      (node (ref "IC6") (pin "2") (pinfunction "IN_2") (pintype "bidirectional"))
      (node (ref "JP4") (pin "1") (pinfunction "1_1") (pintype "passive"))
      (node (ref "L4") (pin "2") (pinfunction "2_2") (pintype "passive"))
    )
    (net (code "109") (name "VREFP") (class "Default")
      (node (ref "C22") (pin "1") (pinfunction "1_1") (pintype "passive"))
      (node (ref "C23") (pin "1") (pinfunction "1_1") (pintype "passive"))
      (node (ref "IC1") (pin "24") (pinfunction "VREFP_24") (pintype "bidirectional"))
      (node (ref "TP4") (pin "1") (pinfunction "1_1") (pintype "passive"))
    )
    (net (code "110") (name "unconnected-(IC1-BIASREF-Pad60)") (class "Default")
      (node (ref "IC1") (pin "60") (pinfunction "BIASREF_60") (pintype "input"))
    )
    (net (code "111") (name "unconnected-(IC1-NC-Pad27)") (class "Default")
      (node (ref "IC1") (pin "27") (pinfunction "NC_27") (pintype "no_connect"))
    )
    (net (code "112") (name "unconnected-(IC1-NC-Pad29)") (class "Default")
      (node (ref "IC1") (pin "29") (pinfunction "NC_29") (pintype "no_connect"))
    )
    (net (code "113") (name "unconnected-(IC1-NC-Pad64)") (class "Default")
      (node (ref "IC1") (pin "64") (pinfunction "NC_64") (pintype "no_connect"))
    )
    (net (code "114") (name "unconnected-(IC1-RESV1-Pad31)") (class "Default")
      (node (ref "IC1") (pin "31") (pinfunction "RESV1_31") (pintype "no_connect"))
    )
    (net (code "115") (name "unconnected-(JP3-Pad5)") (class "Default")
      (node (ref "JP3") (pin "5") (pinfunction "5_5") (pintype "passive"))
    )
    (net (code "116") (name "unconnected-(JP3-Pad6)") (class "Default")
      (node (ref "JP3") (pin "6") (pinfunction "6_6") (pintype "passive"))
    )
    (net (code "117") (name "unconnected-(JP3-Pad7)") (class "Default")
      (node (ref "JP3") (pin "7") (pinfunction "7_7") (pintype "passive"))
    )
    (net (code "118") (name "unconnected-(JP3-Pad8)") (class "Default")
      (node (ref "JP3") (pin "8") (pinfunction "8_8") (pintype "passive"))
    )
    (net (code "119") (name "unconnected-(JP20-Pad1)") (class "Default")
      (node (ref "JP20") (pin "1") (pinfunction "1_1") (pintype "passive"))
    )
    (net (code "120") (name "unconnected-(JP20-Pad2)") (class "Default")
      (node (ref "JP20") (pin "2") (pinfunction "2_2") (pintype "passive"))
    )
    (net (code "121") (name "unconnected-(JP20-Pad3)") (class "Default")
      (node (ref "JP20") (pin "3") (pinfunction "3_3") (pintype "passive"))
    )
    (net (code "122") (name "unconnected-(JP20-Pad4)") (class "Default")
      (node (ref "JP20") (pin "4") (pinfunction "4_4") (pintype "passive"))
    )
    (net (code "123") (name "unconnected-(JP20-Pad5)") (class "Default")
      (node (ref "JP20") (pin "5") (pinfunction "5_5") (pintype "passive"))
    )
    (net (code "124") (name "unconnected-(JP20-Pad6)") (class "Default")
      (node (ref "JP20") (pin "6") (pinfunction "6_6") (pintype "passive"))
    )
    (net (code "125") (name "unconnected-(JP20-Pad7)") (class "Default")
      (node (ref "JP20") (pin "7") (pinfunction "7_7") (pintype "passive"))
    )
    (net (code "126") (name "unconnected-(JP20-Pad9)") (class "Default")
      (node (ref "JP20") (pin "9") (pinfunction "9_9") (pintype "passive"))
    )
    (net (code "127") (name "unconnected-(JP20-Pad10)") (class "Default")
      (node (ref "JP20") (pin "10") (pinfunction "10_10") (pintype "passive"))
    )
    (net (code "128") (name "unconnected-(JP21-Pad1)") (class "Default")
      (node (ref "JP21") (pin "1") (pinfunction "1_1") (pintype "passive"))
    )
    (net (code "129") (name "unconnected-(JP21-Pad2)") (class "Default")
      (node (ref "JP21") (pin "2") (pinfunction "2_2") (pintype "passive"))
    )
    (net (code "130") (name "unconnected-(JP21-Pad3)") (class "Default")
      (node (ref "JP21") (pin "3") (pinfunction "3_3") (pintype "passive"))
    )
    (net (code "131") (name "unconnected-(JP21-Pad5)") (class "Default")
      (node (ref "JP21") (pin "5") (pinfunction "5_5") (pintype "passive"))
    )
    (net (code "132") (name "unconnected-(JP21-Pad6)") (class "Default")
      (node (ref "JP21") (pin "6") (pinfunction "6_6") (pintype "passive"))
    )
    (net (code "133") (name "unconnected-(JP21-Pad7)") (class "Default")
      (node (ref "JP21") (pin "7") (pinfunction "7_7") (pintype "passive"))
    )
    (net (code "134") (name "unconnected-(JP21-Pad8)") (class "Default")
      (node (ref "JP21") (pin "8") (pinfunction "8_8") (pintype "passive"))
    )
    (net (code "135") (name "unconnected-(JP22-Pad1)") (class "Default")
      (node (ref "JP22") (pin "1") (pinfunction "1_1") (pintype "passive"))
    )
    (net (code "136") (name "unconnected-(JP22-Pad2)") (class "Default")
      (node (ref "JP22") (pin "2") (pinfunction "2_2") (pintype "passive"))
    )
    (net (code "137") (name "unconnected-(JP22-Pad5)") (class "Default")
      (node (ref "JP22") (pin "5") (pinfunction "5_5") (pintype "passive"))
    )
    (net (code "138") (name "unconnected-(JP22-Pad6)") (class "Default")
      (node (ref "JP22") (pin "6") (pinfunction "6_6") (pintype "passive"))
    )
    (net (code "139") (name "unconnected-(JP23-Pad1)") (class "Default")
      (node (ref "JP23") (pin "1") (pinfunction "1_1") (pintype "passive"))
    )
    (net (code "140") (name "unconnected-(JP23-Pad2)") (class "Default")
      (node (ref "JP23") (pin "2") (pinfunction "2_2") (pintype "passive"))
    )
    (net (code "141") (name "unconnected-(JP23-Pad3)") (class "Default")
      (node (ref "JP23") (pin "3") (pinfunction "3_3") (pintype "passive"))
    )
    (net (code "142") (name "unconnected-(JP23-Pad9)") (class "Default")
      (node (ref "JP23") (pin "9") (pinfunction "9_9") (pintype "passive"))
    )
    (net (code "143") (name "unconnected-(JP23-Pad10)") (class "Default")
      (node (ref "JP23") (pin "10") (pinfunction "10_10") (pintype "passive"))
    )
    (net (code "144") (name "unconnected-(JP23-Pad15)") (class "Default")
      (node (ref "JP23") (pin "15") (pinfunction "15_15") (pintype "passive"))
    )
    (net (code "145") (name "unconnected-(JP23-Pad16)") (class "Default")
      (node (ref "JP23") (pin "16") (pinfunction "16_16") (pintype "passive"))
    )
    (net (code "146") (name "unconnected-(JP23-Pad17)") (class "Default")
      (node (ref "JP23") (pin "17") (pinfunction "17_17") (pintype "passive"))
    )
    (net (code "147") (name "unconnected-(JP23-Pad18)") (class "Default")
      (node (ref "JP23") (pin "18") (pinfunction "18_18") (pintype "passive"))
    )
    (net (code "148") (name "unconnected-(JP23-Pad19)") (class "Default")
      (node (ref "JP23") (pin "19") (pinfunction "19_19") (pintype "passive"))
    )
    (net (code "149") (name "unconnected-(JP23-Pad20)") (class "Default")
      (node (ref "JP23") (pin "20") (pinfunction "20_20") (pintype "passive"))
    )
    (net (code "150") (name "unconnected-(JP23-Pad21)") (class "Default")
      (node (ref "JP23") (pin "21") (pinfunction "21_21") (pintype "passive"))
    )
    (net (code "151") (name "unconnected-(JP23-Pad22)") (class "Default")
      (node (ref "JP23") (pin "22") (pinfunction "22_22") (pintype "passive"))
    )
    (net (code "152") (name "unconnected-(JP23-Pad23)") (class "Default")
      (node (ref "JP23") (pin "23") (pinfunction "23_23") (pintype "passive"))
    )
    (net (code "153") (name "unconnected-(JP23-Pad24)") (class "Default")
      (node (ref "JP23") (pin "24") (pinfunction "24_24") (pintype "passive"))
    )
    (net (code "154") (name "unconnected-(JP23-Pad25)") (class "Default")
      (node (ref "JP23") (pin "25") (pinfunction "25_25") (pintype "passive"))
    )
    (net (code "155") (name "unconnected-(JP23-Pad26)") (class "Default")
      (node (ref "JP23") (pin "26") (pinfunction "26_26") (pintype "passive"))
    )
    (net (code "156") (name "unconnected-(JP23-Pad30)") (class "Default")
      (node (ref "JP23") (pin "30") (pinfunction "30_30") (pintype "passive"))
    )
    (net (code "157") (name "unconnected-(JP23-Pad31)") (class "Default")
      (node (ref "JP23") (pin "31") (pinfunction "31_31") (pintype "passive"))
    )
    (net (code "158") (name "unconnected-(JP23-Pad32)") (class "Default")
      (node (ref "JP23") (pin "32") (pinfunction "32_32") (pintype "passive"))
    )
    (net (code "159") (name "unconnected-(JP23-Pad34)") (class "Default")
      (node (ref "JP23") (pin "34") (pinfunction "34_34") (pintype "passive"))
    )
    (net (code "160") (name "unconnected-(JP24-Pad1)") (class "Default")
      (node (ref "JP24") (pin "1") (pinfunction "1_1") (pintype "passive"))
    )
    (net (code "161") (name "unconnected-(JP24-Pad2)") (class "Default")
      (node (ref "JP24") (pin "2") (pinfunction "2_2") (pintype "passive"))
    )
    (net (code "162") (name "unconnected-(JP24-Pad3)") (class "Default")
      (node (ref "JP24") (pin "3") (pinfunction "3_3") (pintype "passive"))
    )
    (net (code "163") (name "unconnected-(JP24-Pad4)") (class "Default")
      (node (ref "JP24") (pin "4") (pinfunction "4_4") (pintype "passive"))
    )
    (net (code "164") (name "unconnected-(JP24-Pad5)") (class "Default")
      (node (ref "JP24") (pin "5") (pinfunction "5_5") (pintype "passive"))
    )
    (net (code "165") (name "unconnected-(JP24-Pad6)") (class "Default")
      (node (ref "JP24") (pin "6") (pinfunction "6_6") (pintype "passive"))
    )
    (net (code "166") (name "unconnected-(JP24-Pad7)") (class "Default")
      (node (ref "JP24") (pin "7") (pinfunction "7_7") (pintype "passive"))
    )
    (net (code "167") (name "unconnected-(JP24-Pad8)") (class "Default")
      (node (ref "JP24") (pin "8") (pinfunction "8_8") (pintype "passive"))
    )
    (net (code "168") (name "unconnected-(JP25-Pad2)") (class "Default")
      (node (ref "JP25") (pin "2") (pinfunction "2_2") (pintype "passive"))
    )
    (net (code "169") (name "unconnected-(JP25-Pad3)") (class "Default")
      (node (ref "JP25") (pin "3") (pinfunction "3_3") (pintype "passive"))
    )
    (net (code "170") (name "unconnected-(JP25-Pad4)") (class "Default")
      (node (ref "JP25") (pin "4") (pinfunction "4_4") (pintype "passive"))
    )
    (net (code "171") (name "unconnected-(JP25-Pad6)") (class "Default")
      (node (ref "JP25") (pin "6") (pinfunction "6_6") (pintype "passive"))
    )
    (net (code "172") (name "unconnected-(JP25-Pad7)") (class "Default")
      (node (ref "JP25") (pin "7") (pinfunction "7_7") (pintype "passive"))
    )
    (net (code "173") (name "unconnected-(JP26-Pad1)") (class "Default")
      (node (ref "JP26") (pin "1") (pinfunction "1_1") (pintype "passive"))
    )
    (net (code "174") (name "unconnected-(JP26-Pad3)") (class "Default")
      (node (ref "JP26") (pin "3") (pinfunction "3_3") (pintype "passive"))
    )
    (net (code "175") (name "unconnected-(JP26-Pad5)") (class "Default")
      (node (ref "JP26") (pin "5") (pinfunction "5_5") (pintype "passive"))
    )
    (net (code "176") (name "unconnected-(JP26-Pad6)") (class "Default")
      (node (ref "JP26") (pin "6") (pinfunction "6_6") (pintype "passive"))
    )
    (net (code "177") (name "unconnected-(JP26-Pad7)") (class "Default")
      (node (ref "JP26") (pin "7") (pinfunction "7_7") (pintype "passive"))
    )
    (net (code "178") (name "unconnected-(JP26-Pad8)") (class "Default")
      (node (ref "JP26") (pin "8") (pinfunction "8_8") (pintype "passive"))
    )
    (net (code "179") (name "~{ADC_CS_0}") (class "Default")
      (node (ref "JP2") (pin "10") (pinfunction "10_10") (pintype "passive"))
      (node (ref "JP21") (pin "4") (pinfunction "4_4") (pintype "passive"))
    )
    (net (code "180") (name "~{ADC_CS_1}") (class "Default")
      (node (ref "JP2") (pin "12") (pinfunction "12_12") (pintype "passive"))
      (node (ref "JP20") (pin "8") (pinfunction "8_8") (pintype "passive"))
    )
    (net (code "181") (name "~{ADC_CS_2}") (class "Default")
      (node (ref "JP2") (pin "14") (pinfunction "14_14") (pintype "passive"))
      (node (ref "JP23") (pin "33") (pinfunction "33_33") (pintype "passive"))
    )
    (net (code "182") (name "~{ADC_CS_3}") (class "Default")
      (node (ref "JP2") (pin "16") (pinfunction "16_16") (pintype "passive"))
      (node (ref "JP23") (pin "4") (pinfunction "4_4") (pintype "passive"))
    )
    (net (code "183") (name "~{ADC_PWDN_0}") (class "Default")
      (node (ref "JP1") (pin "22") (pinfunction "22_22") (pintype "passive"))
      (node (ref "JP23") (pin "13") (pinfunction "13_13") (pintype "passive"))
    )
    (net (code "184") (name "~{ADC_PWDN_1}") (class "Default")
      (node (ref "JP1") (pin "24") (pinfunction "24_24") (pintype "passive"))
      (node (ref "JP23") (pin "14") (pinfunction "14_14") (pintype "passive"))
    )
    (net (code "185") (name "~{ADC_RESET_0}") (class "Default")
      (node (ref "JP1") (pin "18") (pinfunction "18_18") (pintype "passive"))
      (node (ref "JP23") (pin "27") (pinfunction "27_27") (pintype "passive"))
    )
    (net (code "186") (name "~{ADC_RESET_1}") (class "Default")
      (node (ref "JP1") (pin "20") (pinfunction "20_20") (pintype "passive"))
      (node (ref "JP23") (pin "28") (pinfunction "28_28") (pintype "passive"))
    )
    (net (code "187") (name "~{ADS_PWDN}") (class "Default")
      (node (ref "IC11") (pin "15") (pinfunction "B5_15") (pintype "bidirectional"))
      (node (ref "JP1") (pin "21") (pinfunction "21_21") (pintype "passive"))
      (node (ref "JP1") (pin "23") (pinfunction "23_23") (pintype "passive"))
    )
    (net (code "188") (name "~{ADS_RESET}") (class "Default")
      (node (ref "IC11") (pin "20") (pinfunction "B1_20") (pintype "bidirectional"))
      (node (ref "JP1") (pin "17") (pinfunction "17_17") (pintype "passive"))
      (node (ref "JP1") (pin "19") (pinfunction "19_19") (pintype "passive"))
    )
    (net (code "189") (name "~{ADS_SPI_CS}") (class "Default")
      (node (ref "IC11") (pin "14") (pinfunction "B6_14") (pintype "bidirectional"))
      (node (ref "JP2") (pin "11") (pinfunction "11_11") (pintype "passive"))
      (node (ref "JP2") (pin "13") (pinfunction "13_13") (pintype "passive"))
      (node (ref "JP2") (pin "15") (pinfunction "15_15") (pintype "passive"))
      (node (ref "JP2") (pin "9") (pinfunction "9_9") (pintype "passive"))
    )
    (net (code "190") (name "~{PWDN}") (class "Default")
      (node (ref "IC1") (pin "35") (pinfunction "~{PWDN}_35") (pintype "input"))
      (node (ref "IC11") (pin "6") (pinfunction "A5_6") (pintype "bidirectional"))
    )
    (net (code "191") (name "~{RESET}") (class "Default")
      (node (ref "IC1") (pin "36") (pinfunction "~{RESET}_36") (pintype "input"))
      (node (ref "IC11") (pin "1") (pinfunction "A1_1") (pintype "bidirectional"))
    )
    (net (code "192") (name "~{SPI_CS}") (class "Default")
      (node (ref "IC1") (pin "39") (pinfunction "~{CS}_39") (pintype "input"))
      (node (ref "IC11") (pin "7") (pinfunction "A6_7") (pintype "bidirectional"))
    )
  )
)
